# main.net
KiCad netlist of a schematic drawn in EAGLE
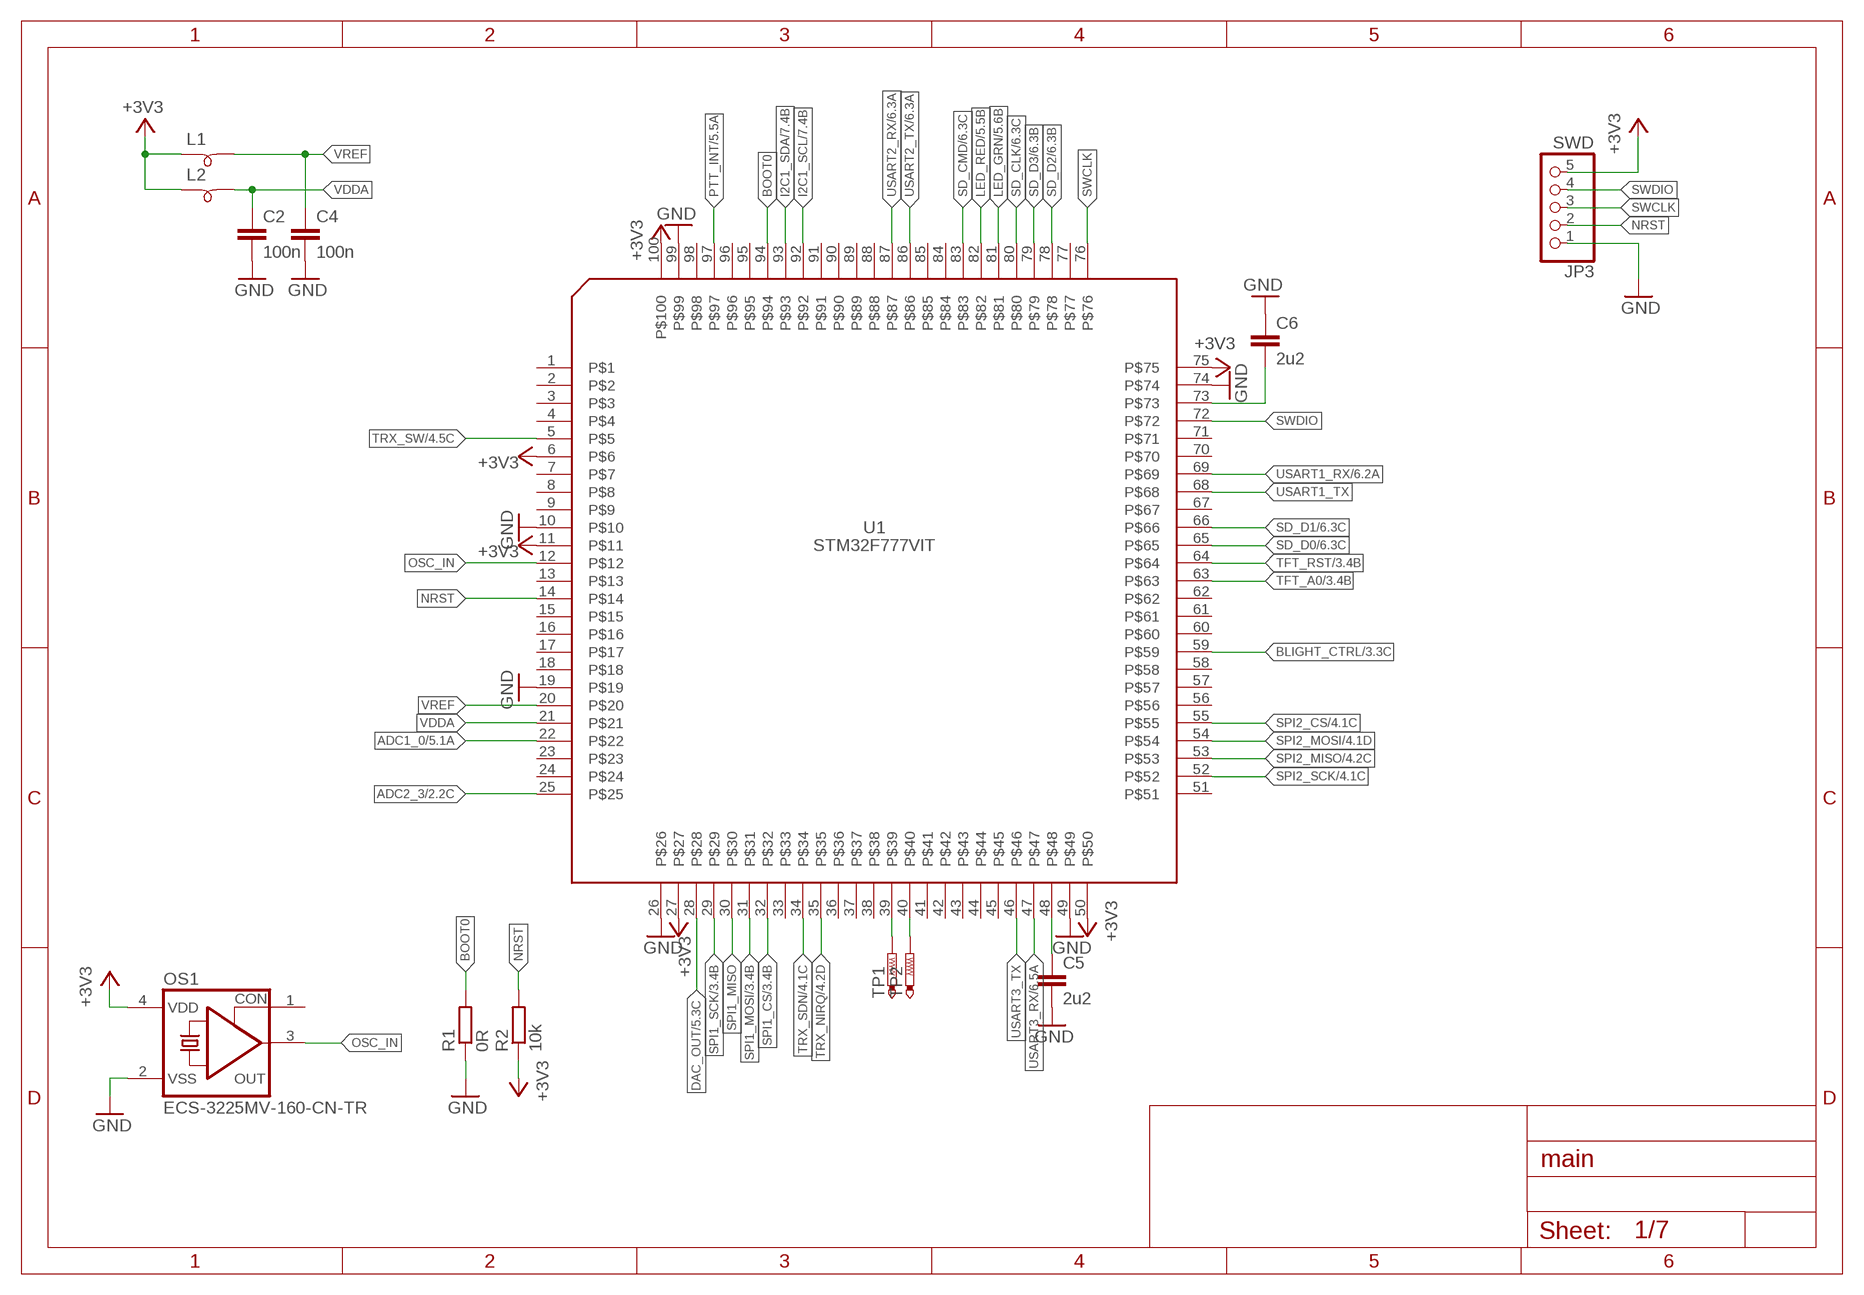
[diagram p0: schematic, sheet 1]
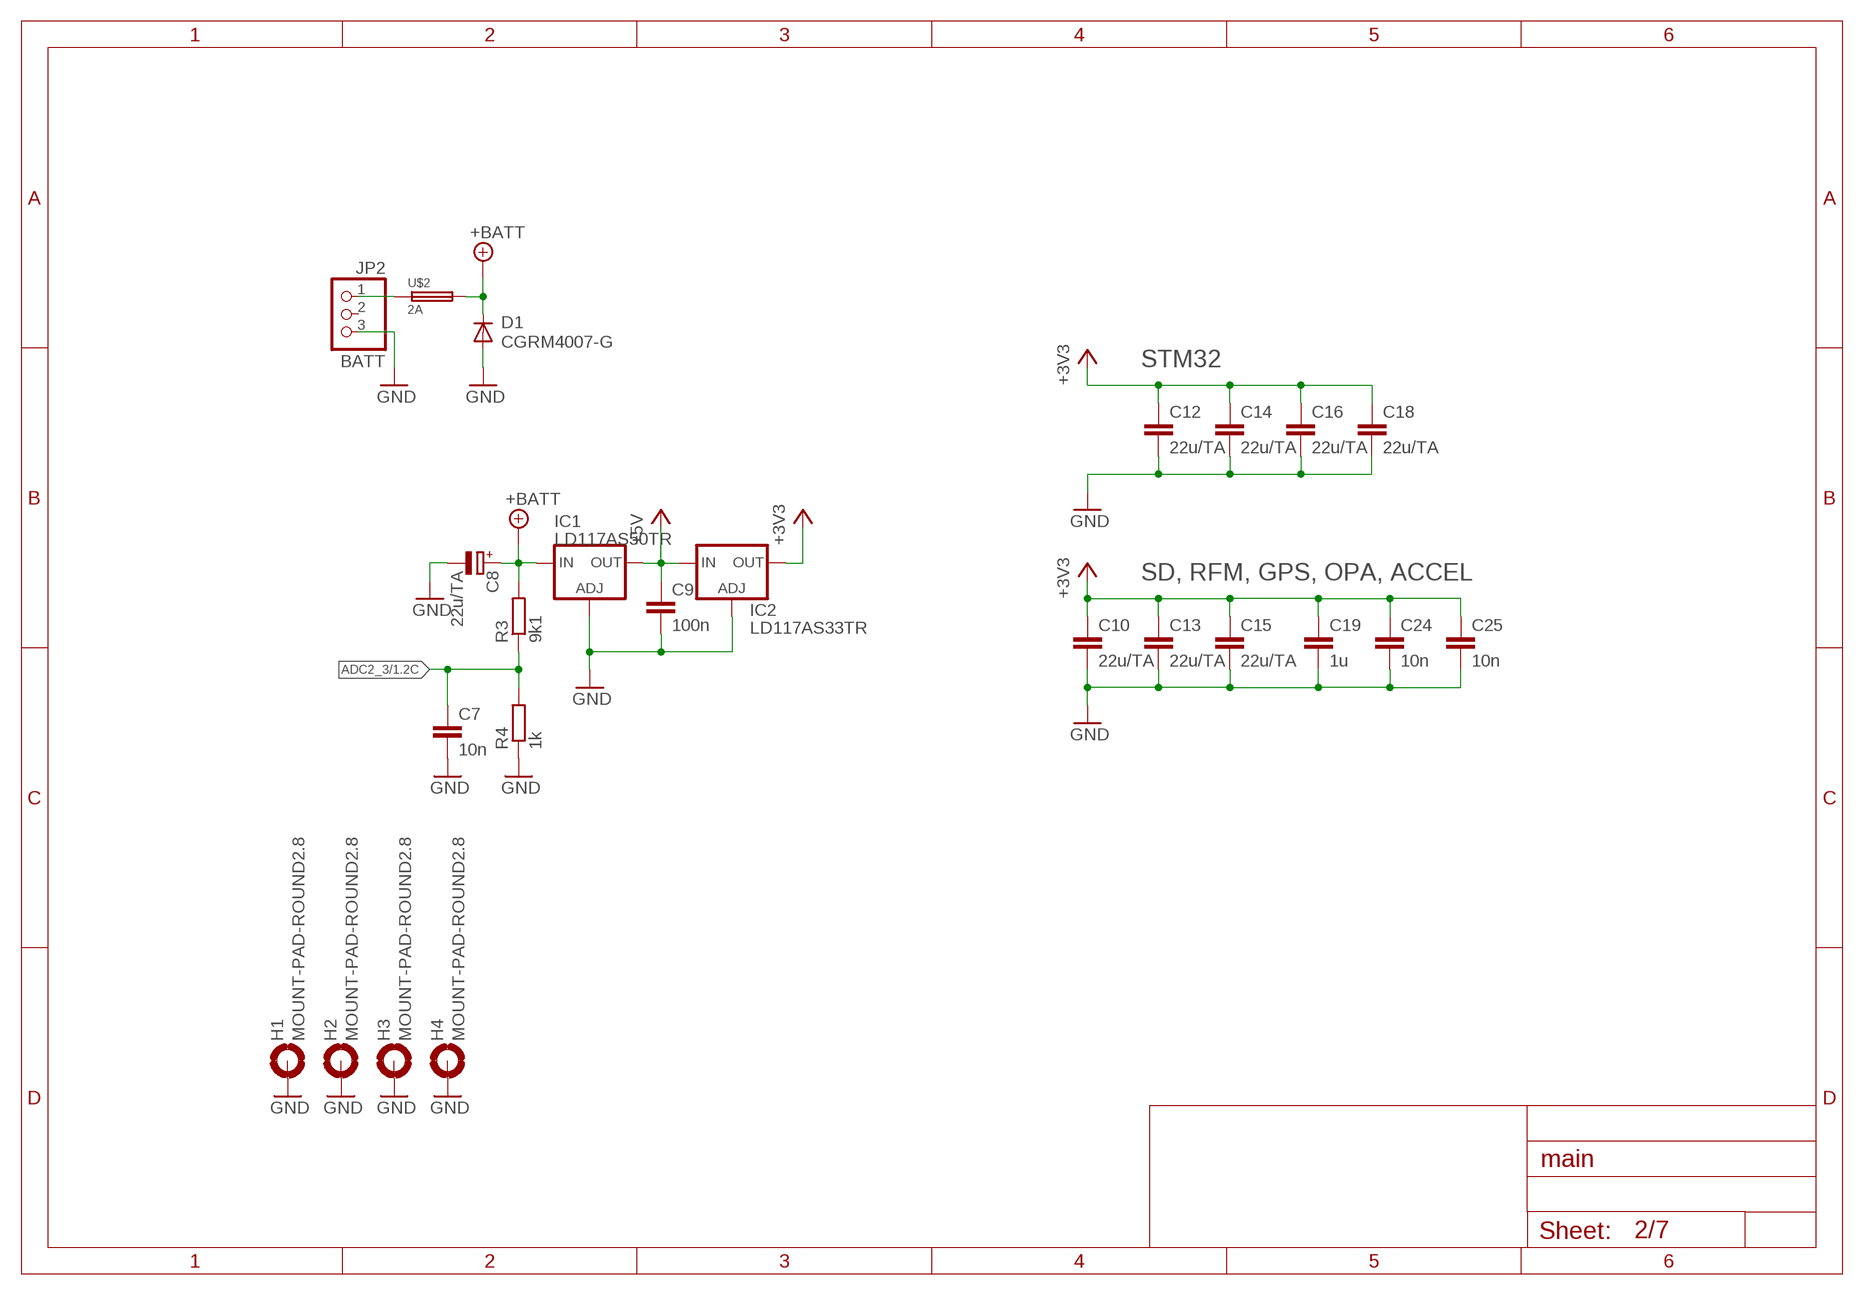
[diagram p1: schematic, sheet 2]
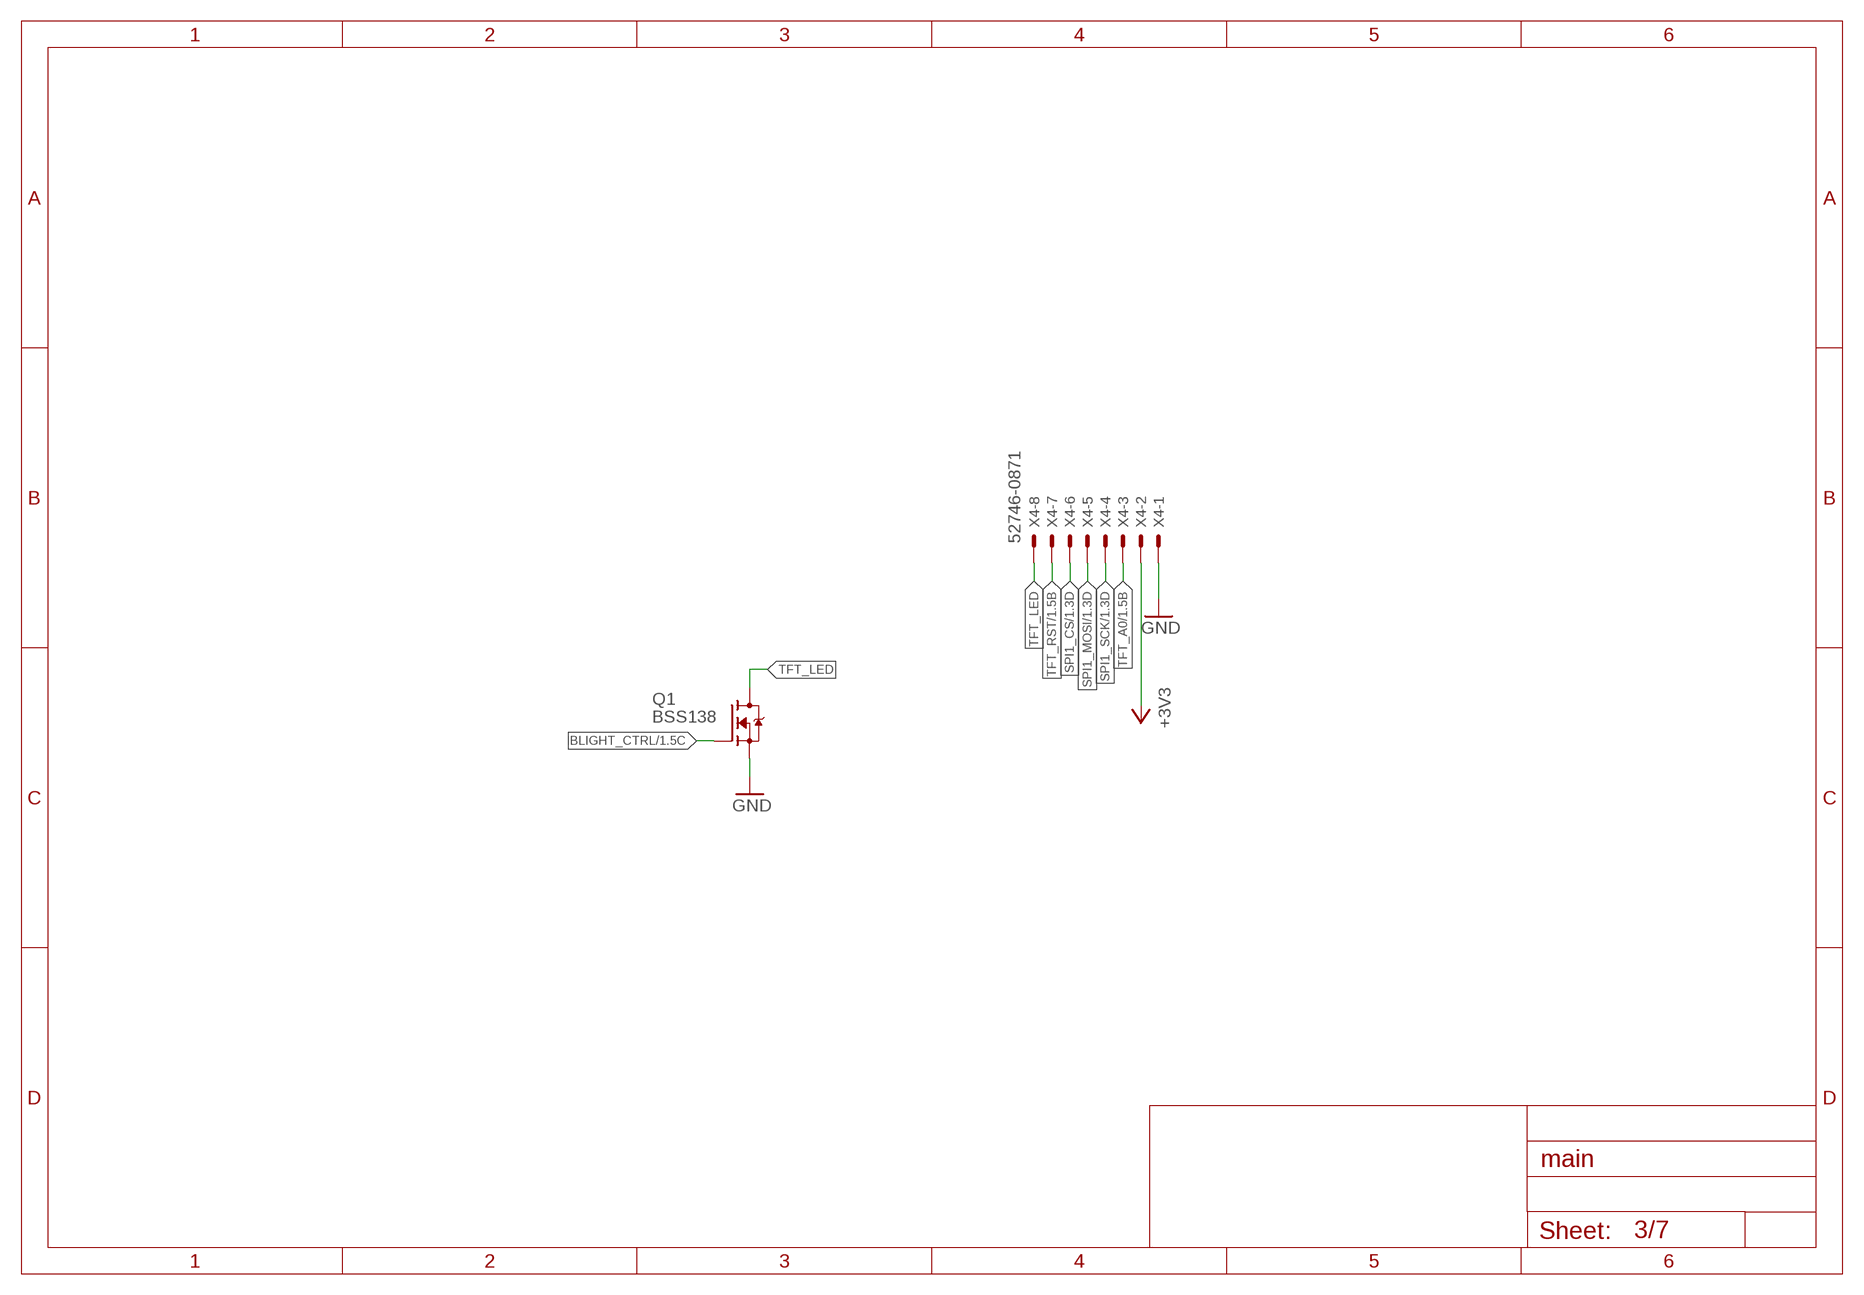
[diagram p2: schematic, sheet 3]
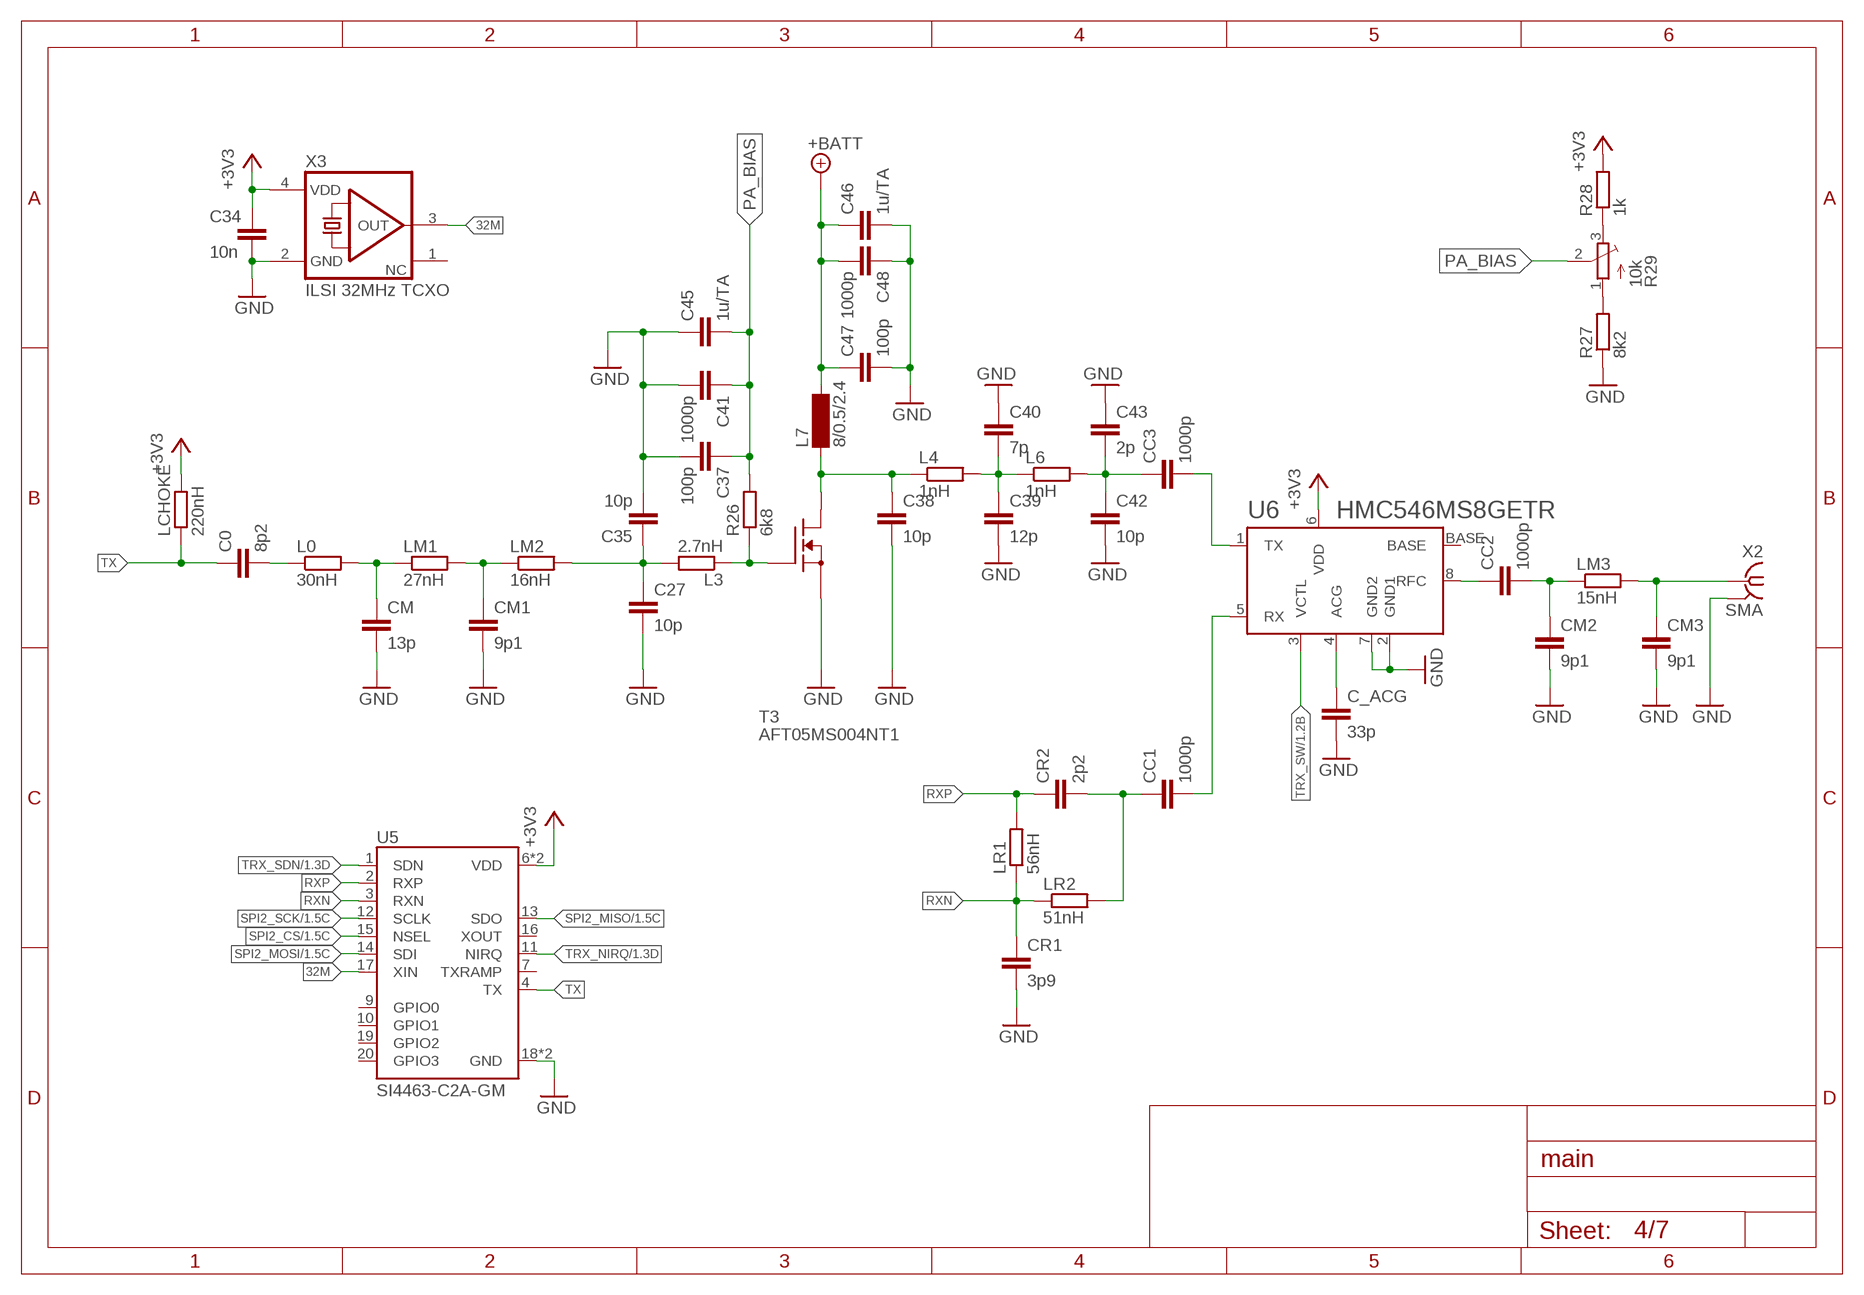
[diagram p3: schematic, sheet 4]
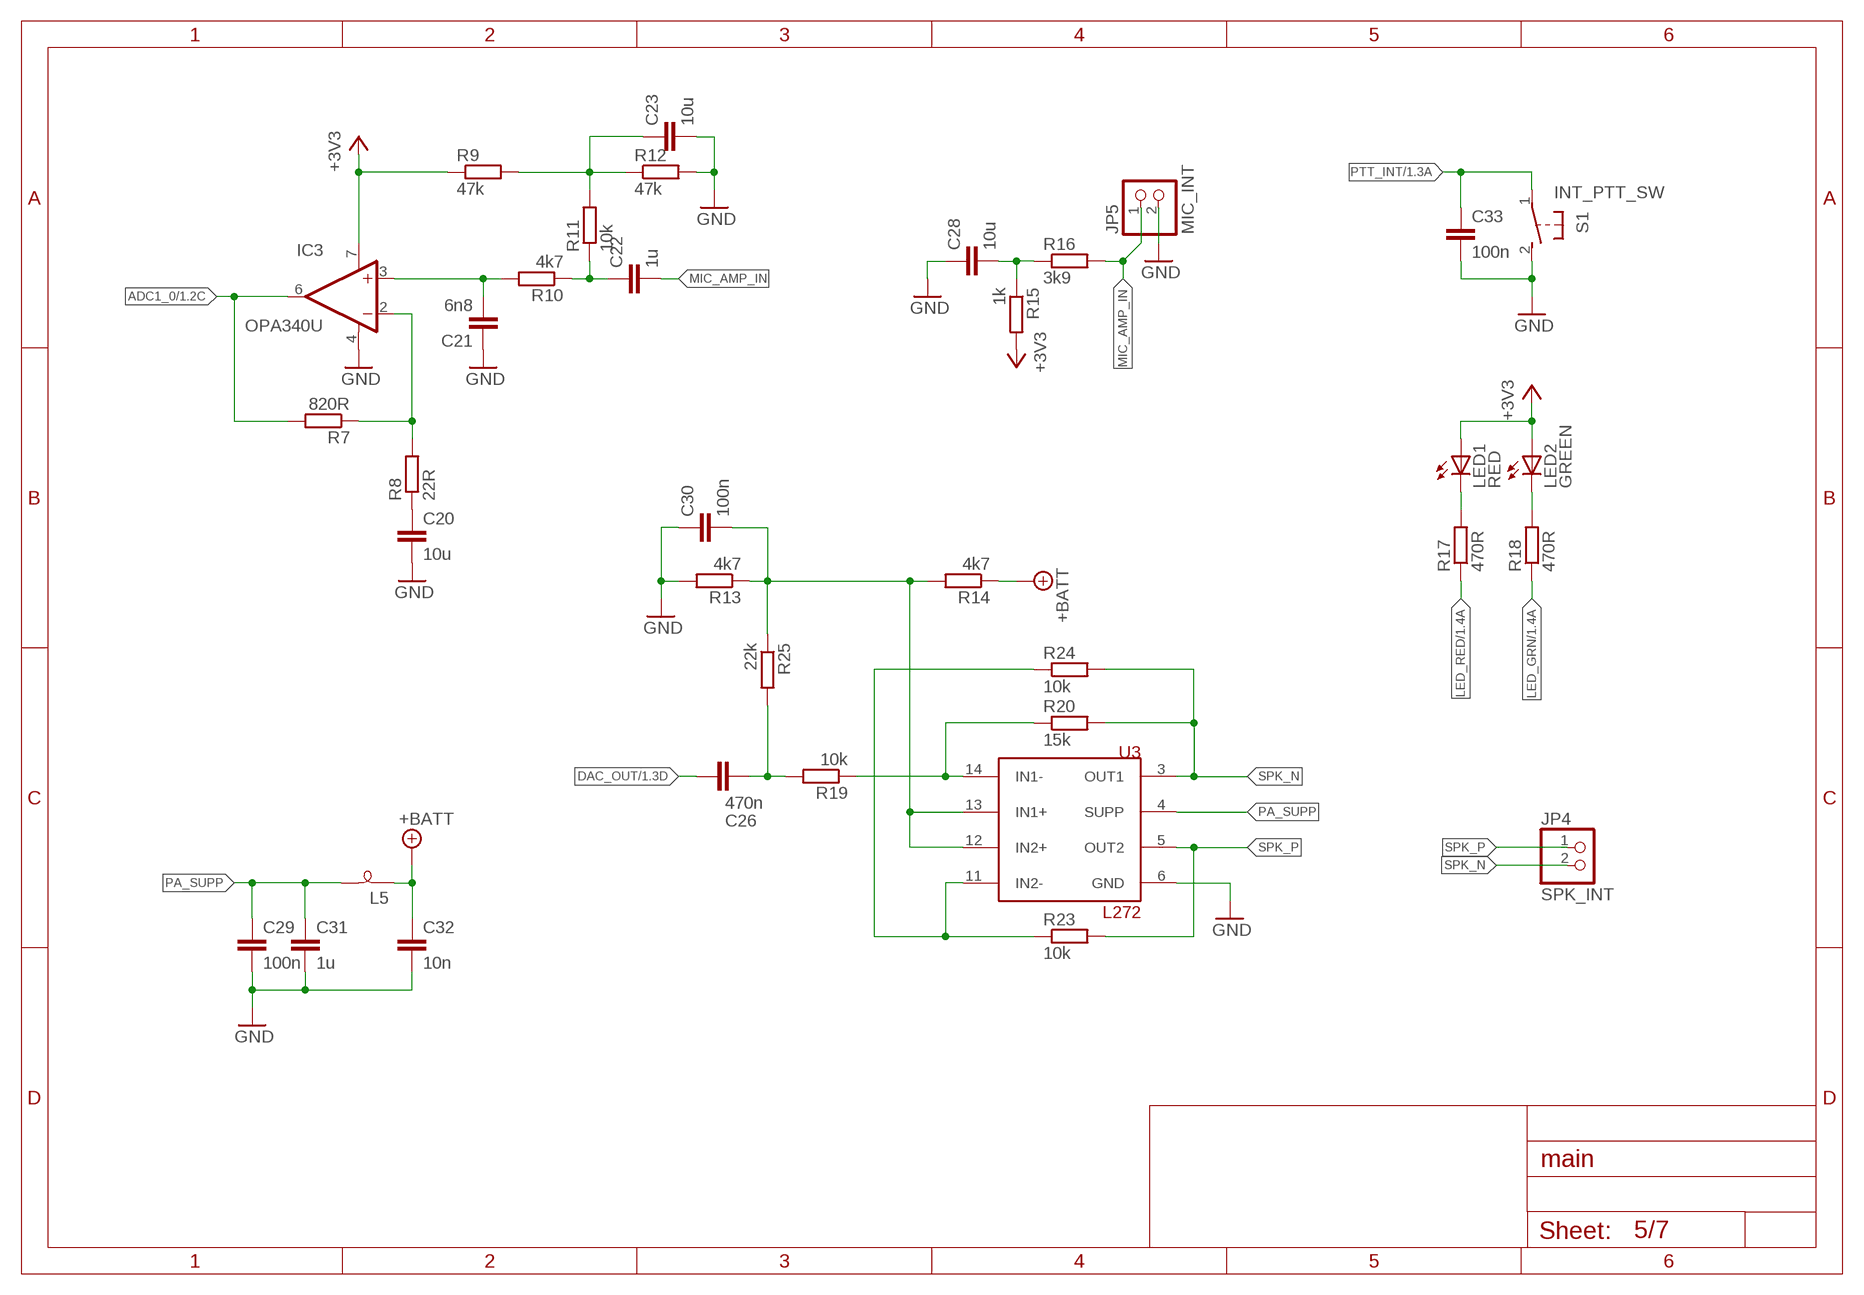
[diagram p4: schematic, sheet 5]
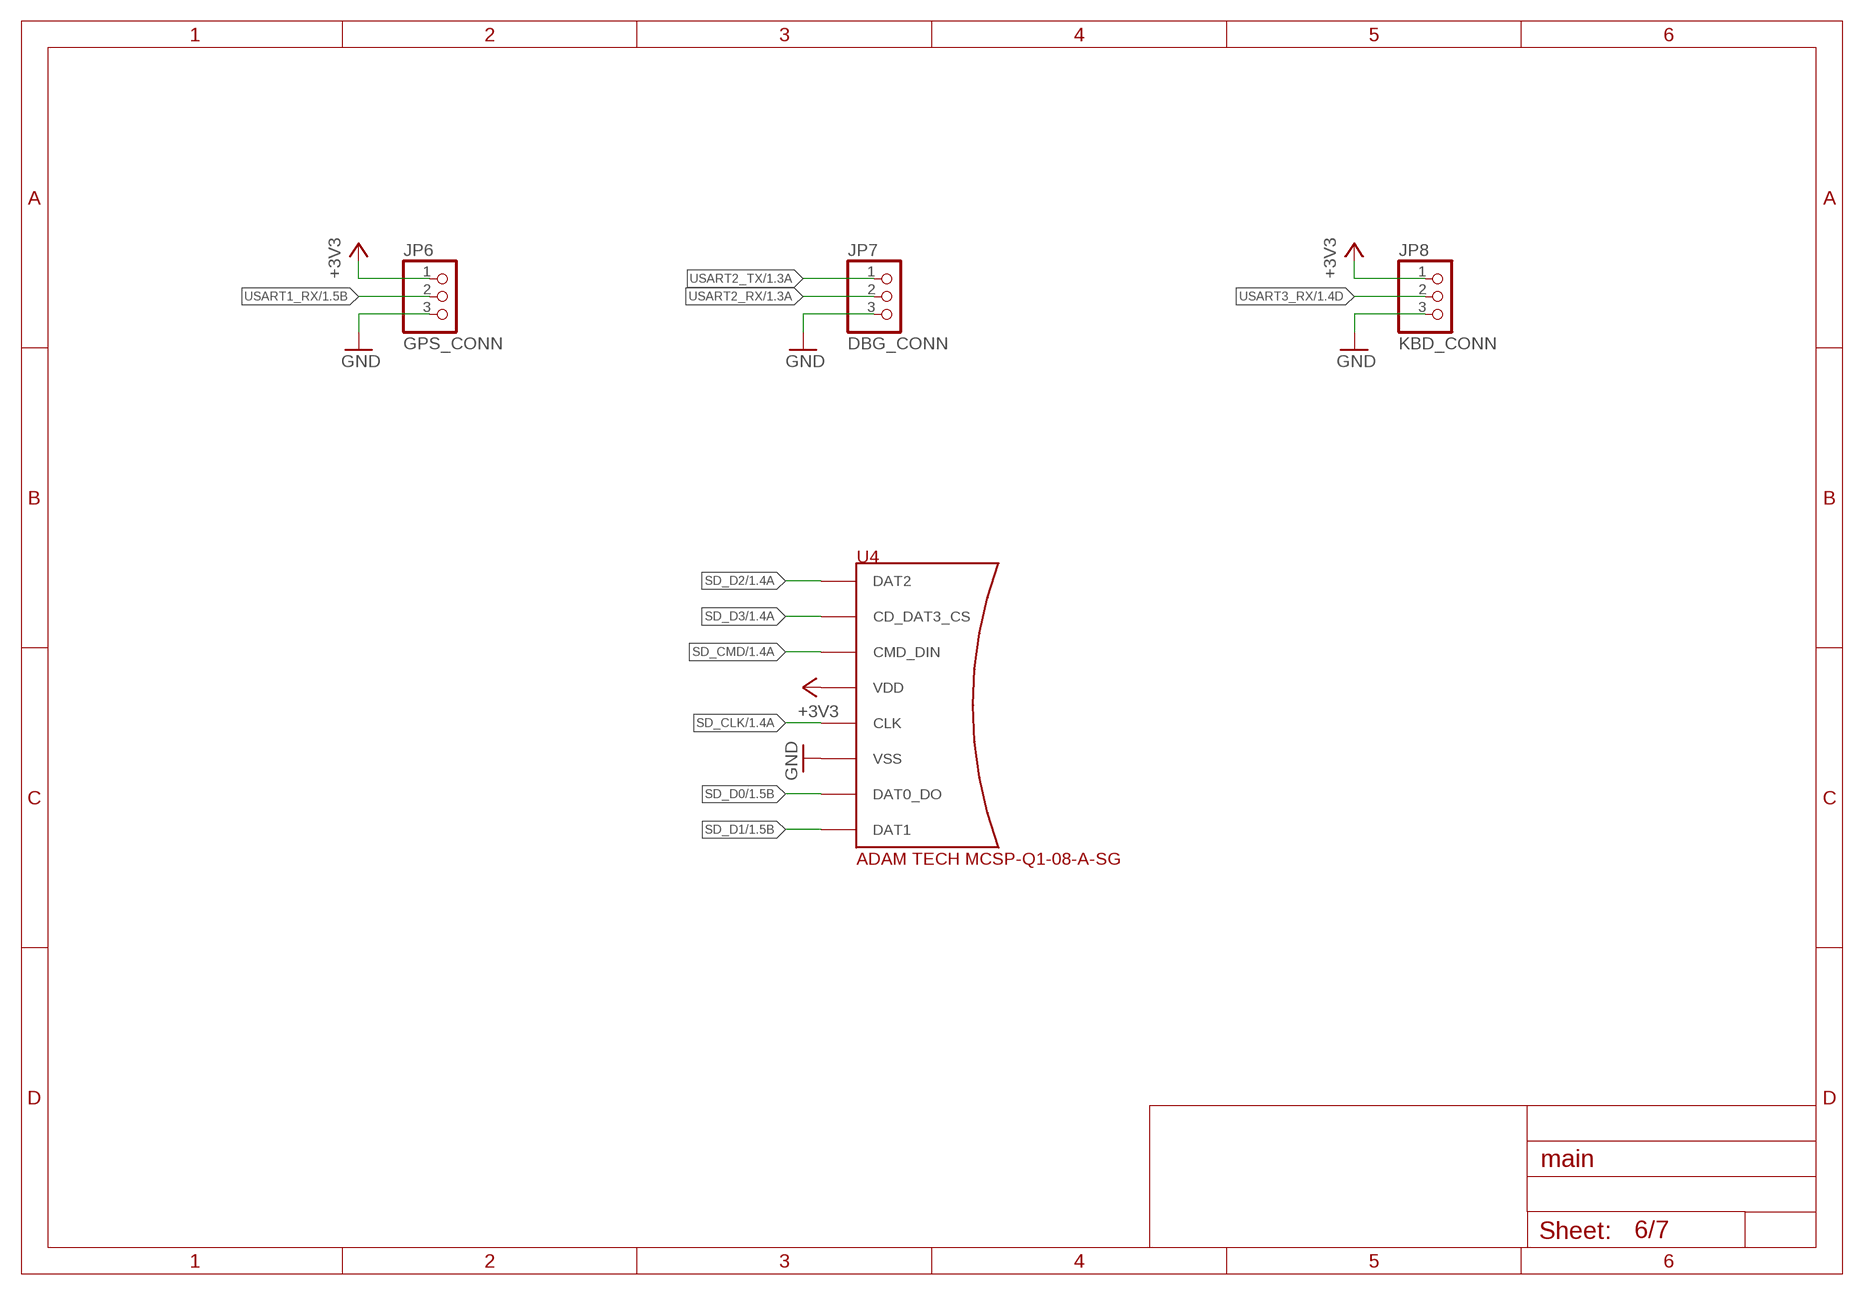
[diagram p5: schematic, sheet 6]
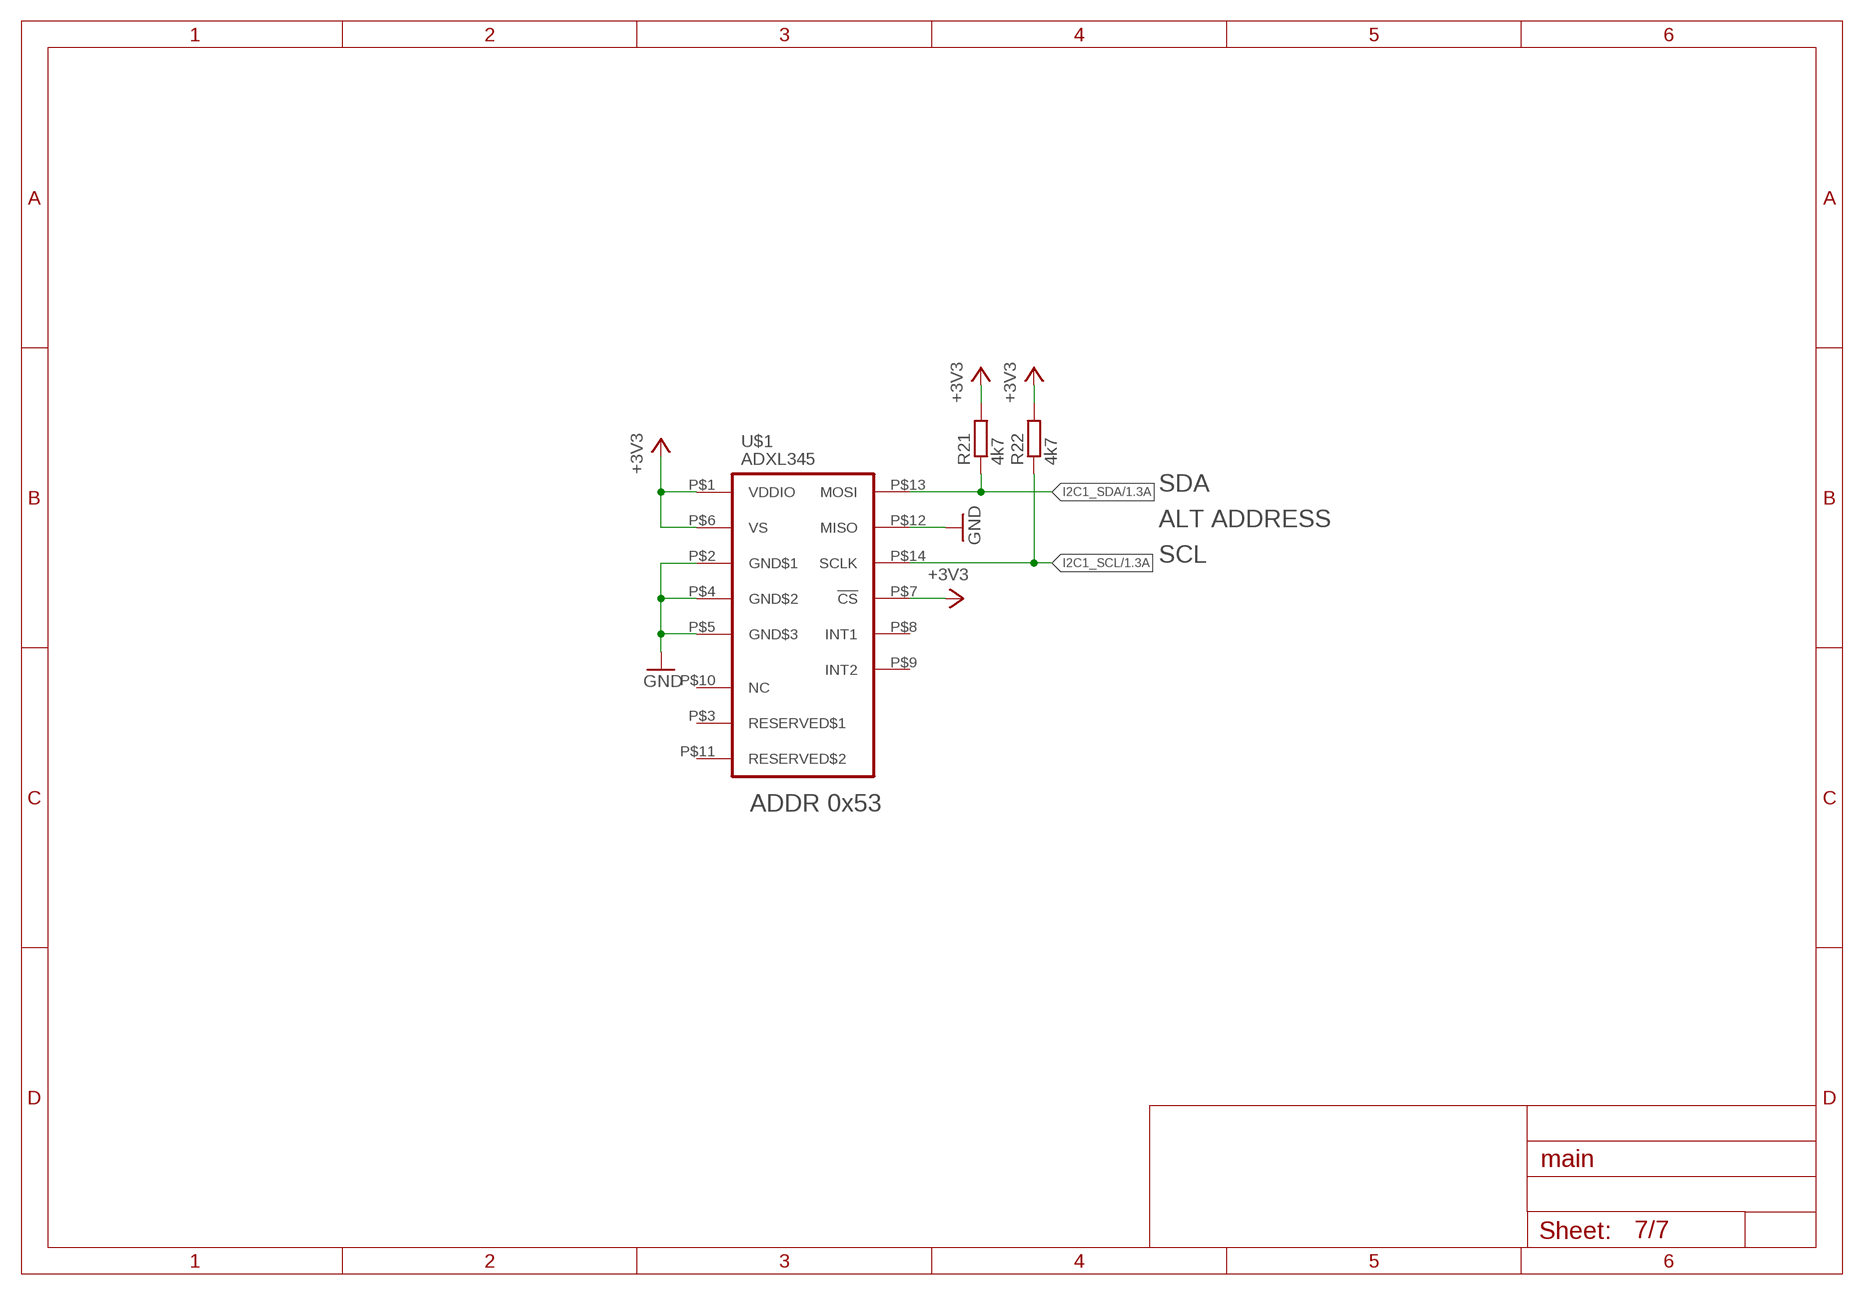
[diagram p6: schematic, sheet 7]

(export (version "E")
  (design (tool "Eeschema 10.0.6"))
  (components
    (comp (ref "C20")
      (value "10u")
      (footprint "eagle-import:C1206")
      (libsource (lib "eagle-import") (part "C-EUC1206"))
    )
    (comp (ref "C21")
      (value "6n8")
      (footprint "eagle-import:C0805")
      (libsource (lib "eagle-import") (part "C-EUC0805"))
    )
    (comp (ref "C22")
      (value "1u")
      (footprint "eagle-import:C1206")
      (libsource (lib "eagle-import") (part "C-EUC1206"))
    )
    (comp (ref "C23")
      (value "10u")
      (footprint "eagle-import:C1206")
      (libsource (lib "eagle-import") (part "C-EUC1206"))
    )
    (comp (ref "C26")
      (value "470n")
      (footprint "eagle-import:C0805")
      (libsource (lib "eagle-import") (part "C-EUC0805"))
    )
    (comp (ref "C28")
      (value "10u")
      (footprint "eagle-import:C1206")
      (libsource (lib "eagle-import") (part "C-EUC1206"))
    )
    (comp (ref "C29")
      (value "100n")
      (footprint "eagle-import:C1206")
      (libsource (lib "eagle-import") (part "C-EUC1206"))
    )
    (comp (ref "C30")
      (value "100n")
      (footprint "eagle-import:C1206")
      (libsource (lib "eagle-import") (part "C-EUC1206"))
    )
    (comp (ref "C31")
      (value "1u")
      (footprint "eagle-import:C1206")
      (libsource (lib "eagle-import") (part "C-EUC1206"))
    )
    (comp (ref "C32")
      (value "10n")
      (footprint "eagle-import:C0805")
      (libsource (lib "eagle-import") (part "C-EUC0805"))
    )
    (comp (ref "C33")
      (value "100n")
      (footprint "eagle-import:C0805")
      (libsource (lib "eagle-import") (part "C-EUC0805"))
    )
    (comp (ref "IC3")
      (value "OPA340U")
      (footprint "eagle-import:SO08")
      (fields (field (name "MPN") "OPA340UA"))
      (libsource (lib "eagle-import") (part "OPA340U"))
    )
    (comp (ref "JP4")
      (value "SPK_INT")
      (footprint "eagle-import:1X02")
      (libsource (lib "eagle-import") (part "PINHD-1X2"))
    )
    (comp (ref "JP5")
      (value "MIC_INT")
      (footprint "eagle-import:1X02")
      (libsource (lib "eagle-import") (part "PINHD-1X2"))
    )
    (comp (ref "L5")
      (value "SM-B5")
      (footprint "eagle-import:SM-B5")
      (libsource (lib "eagle-import") (part "SM-B5"))
    )
    (comp (ref "LED1")
      (value "RED")
      (footprint "eagle-import:CHIPLED_1206")
      (libsource (lib "eagle-import") (part "LEDCHIPLED_1206"))
    )
    (comp (ref "LED2")
      (value "GREEN")
      (footprint "eagle-import:CHIPLED_1206")
      (libsource (lib "eagle-import") (part "LEDCHIPLED_1206"))
    )
    (comp (ref "R7")
      (value "820R")
      (footprint "eagle-import:R0805")
      (libsource (lib "eagle-import") (part "resistor_R-EU_R0805"))
    )
    (comp (ref "R8")
      (value "22R")
      (footprint "eagle-import:R0805")
      (libsource (lib "eagle-import") (part "resistor_R-EU_R0805"))
    )
    (comp (ref "R9")
      (value "47k")
      (footprint "eagle-import:R0805")
      (libsource (lib "eagle-import") (part "resistor_R-EU_R0805"))
    )
    (comp (ref "R10")
      (value "4k7")
      (footprint "eagle-import:R0805")
      (libsource (lib "eagle-import") (part "resistor_R-EU_R0805"))
    )
    (comp (ref "R11")
      (value "10k")
      (footprint "eagle-import:R0805")
      (libsource (lib "eagle-import") (part "resistor_R-EU_R0805"))
    )
    (comp (ref "R12")
      (value "47k")
      (footprint "eagle-import:R0805")
      (libsource (lib "eagle-import") (part "resistor_R-EU_R0805"))
    )
    (comp (ref "R13")
      (value "4k7")
      (footprint "eagle-import:R0805")
      (libsource (lib "eagle-import") (part "resistor_R-EU_R0805"))
    )
    (comp (ref "R14")
      (value "4k7")
      (footprint "eagle-import:R0805")
      (libsource (lib "eagle-import") (part "resistor_R-EU_R0805"))
    )
    (comp (ref "R15")
      (value "1k")
      (footprint "eagle-import:R0805")
      (libsource (lib "eagle-import") (part "resistor_R-EU_R0805"))
    )
    (comp (ref "R16")
      (value "3k9")
      (footprint "eagle-import:R0805")
      (libsource (lib "eagle-import") (part "resistor_R-EU_R0805"))
    )
    (comp (ref "R17")
      (value "470R")
      (footprint "eagle-import:R0805")
      (libsource (lib "eagle-import") (part "resistor_R-EU_R0805"))
    )
    (comp (ref "R18")
      (value "470R")
      (footprint "eagle-import:R0805")
      (libsource (lib "eagle-import") (part "resistor_R-EU_R0805"))
    )
    (comp (ref "R19")
      (value "10k")
      (footprint "eagle-import:R0805")
      (libsource (lib "eagle-import") (part "resistor_R-EU_R0805"))
    )
    (comp (ref "R20")
      (value "15k")
      (footprint "eagle-import:R0805")
      (libsource (lib "eagle-import") (part "resistor_R-EU_R0805"))
    )
    (comp (ref "R23")
      (value "10k")
      (footprint "eagle-import:R0805")
      (libsource (lib "eagle-import") (part "resistor_R-EU_R0805"))
    )
    (comp (ref "R24")
      (value "10k")
      (footprint "eagle-import:R0805")
      (libsource (lib "eagle-import") (part "resistor_R-EU_R0805"))
    )
    (comp (ref "R25")
      (value "22k")
      (footprint "eagle-import:R0805")
      (libsource (lib "eagle-import") (part "resistor_R-EU_R0805"))
    )
    (comp (ref "S1")
      (value "INT_PTT_SW")
      (footprint "eagle-import:B3F-31XX")
      (fields (field (name "MPN") "B3F-3100"))
      (libsource (lib "eagle-import") (part "31-XX"))
    )
    (comp (ref "U3")
      (value "L272")
      (footprint "eagle-import:SO16")
      (libsource (lib "eagle-import") (part "L272"))
    )
    (comp (ref "R21")
      (value "4k7")
      (footprint "eagle-import:R0805")
      (libsource (lib "eagle-import") (part "R-EU_R0805"))
    )
    (comp (ref "R22")
      (value "4k7")
      (footprint "eagle-import:R0805")
      (libsource (lib "eagle-import") (part "R-EU_R0805"))
    )
    (comp (ref "U$1")
      (value "ADXL345")
      (footprint "eagle-import:LGA14")
      (libsource (lib "eagle-import") (part "ADXL345"))
    )
    (comp (ref "Q1")
      (value "BSS138")
      (footprint "eagle-import:SOT23")
      (fields (field (name "MF") "Fairchild"))
      (libsource (lib "eagle-import") (part "BSS138"))
    )
    (comp (ref "X4")
      (value "52746-0871")
      (footprint "eagle-import:52745-0890")
      (fields (field (name "MPN") "52745-0890"))
      (libsource (lib "eagle-import") (part "52745-0890"))
    )
    (comp (ref "C2")
      (value "100n")
      (footprint "eagle-import:C0805")
      (libsource (lib "eagle-import") (part "C-EUC0805"))
    )
    (comp (ref "C4")
      (value "100n")
      (footprint "eagle-import:C0805")
      (libsource (lib "eagle-import") (part "C-EUC0805"))
    )
    (comp (ref "C5")
      (value "2u2")
      (footprint "eagle-import:C1206")
      (libsource (lib "eagle-import") (part "C-EUC1206"))
    )
    (comp (ref "C6")
      (value "2u2")
      (footprint "eagle-import:C1206")
      (libsource (lib "eagle-import") (part "C-EUC1206"))
    )
    (comp (ref "JP3")
      (value "SWD")
      (footprint "eagle-import:1X05_90")
      (libsource (lib "eagle-import") (part "PINHD-1X5/90"))
    )
    (comp (ref "L1")
      (value "SM-B5")
      (footprint "eagle-import:SM-B5")
      (libsource (lib "eagle-import") (part "SM-B5"))
    )
    (comp (ref "L2")
      (value "SM-B5")
      (footprint "eagle-import:SM-B5")
      (libsource (lib "eagle-import") (part "SM-B5"))
    )
    (comp (ref "OS1")
      (value "ECS-3225MV-160-CN-TR")
      (footprint "eagle-import:3.4X2.7-4-PAD")
      (libsource (lib "eagle-import") (part "OSC-OE-CFPS-39"))
    )
    (comp (ref "R1")
      (value "0R")
      (footprint "eagle-import:R0805")
      (libsource (lib "eagle-import") (part "resistor_R-EU_R0805"))
    )
    (comp (ref "R2")
      (value "10k")
      (footprint "eagle-import:R0805")
      (libsource (lib "eagle-import") (part "resistor_R-EU_R0805"))
    )
    (comp (ref "TP1")
      (value "PTR1B1,27")
      (footprint "eagle-import:B1,27")
      (libsource (lib "eagle-import") (part "PTR1B1,27"))
    )
    (comp (ref "TP2")
      (value "PTR1B1,27")
      (footprint "eagle-import:B1,27")
      (libsource (lib "eagle-import") (part "PTR1B1,27"))
    )
    (comp (ref "U1")
      (value "STM32F777VIT")
      (footprint "eagle-import:LQFP100")
      (libsource (lib "eagle-import") (part "STM32F777VIT"))
    )
    (comp (ref "C0")
      (value "8p2")
      (footprint "eagle-import:C0805")
      (libsource (lib "eagle-import") (part "C-EUC0805"))
    )
    (comp (ref "C27")
      (value "10p")
      (footprint "eagle-import:C0805")
      (libsource (lib "eagle-import") (part "C-EUC0805"))
    )
    (comp (ref "C34")
      (value "10n")
      (footprint "eagle-import:C0805")
      (libsource (lib "eagle-import") (part "C-EUC0805"))
    )
    (comp (ref "C35")
      (value "10p")
      (footprint "eagle-import:C0805")
      (libsource (lib "eagle-import") (part "C-EUC0805"))
    )
    (comp (ref "C37")
      (value "100p")
      (footprint "eagle-import:C0805")
      (libsource (lib "eagle-import") (part "C-EUC0805"))
    )
    (comp (ref "C38")
      (value "10p")
      (footprint "eagle-import:C0805")
      (libsource (lib "eagle-import") (part "C-EUC0805"))
    )
    (comp (ref "C39")
      (value "12p")
      (footprint "eagle-import:C0805")
      (libsource (lib "eagle-import") (part "C-EUC0805"))
    )
    (comp (ref "C40")
      (value "7p")
      (footprint "eagle-import:C0805")
      (libsource (lib "eagle-import") (part "C-EUC0805"))
    )
    (comp (ref "C41")
      (value "1000p")
      (footprint "eagle-import:C0805")
      (libsource (lib "eagle-import") (part "C-EUC0805"))
    )
    (comp (ref "C42")
      (value "10p")
      (footprint "eagle-import:C0805")
      (libsource (lib "eagle-import") (part "C-EUC0805"))
    )
    (comp (ref "C43")
      (value "2p")
      (footprint "eagle-import:C0805")
      (libsource (lib "eagle-import") (part "C-EUC0805"))
    )
    (comp (ref "C45")
      (value "1u/TA")
      (footprint "eagle-import:C1206")
      (libsource (lib "eagle-import") (part "resistor_C-EUC1206"))
    )
    (comp (ref "C46")
      (value "1u/TA")
      (footprint "eagle-import:C1206")
      (libsource (lib "eagle-import") (part "resistor_C-EUC1206"))
    )
    (comp (ref "C47")
      (value "100p")
      (footprint "eagle-import:C0805")
      (libsource (lib "eagle-import") (part "C-EUC0805"))
    )
    (comp (ref "C48")
      (value "1000p")
      (footprint "eagle-import:C0805")
      (libsource (lib "eagle-import") (part "C-EUC0805"))
    )
    (comp (ref "CC1")
      (value "1000p")
      (footprint "eagle-import:C0805")
      (libsource (lib "eagle-import") (part "C-EUC0805"))
    )
    (comp (ref "CC2")
      (value "1000p")
      (footprint "eagle-import:C0805")
      (libsource (lib "eagle-import") (part "C-EUC0805"))
    )
    (comp (ref "CC3")
      (value "1000p")
      (footprint "eagle-import:C0805")
      (libsource (lib "eagle-import") (part "C-EUC0805"))
    )
    (comp (ref "CM")
      (value "13p")
      (footprint "eagle-import:C0805")
      (libsource (lib "eagle-import") (part "C-EUC0805"))
    )
    (comp (ref "CM1")
      (value "9p1")
      (footprint "eagle-import:C0805")
      (libsource (lib "eagle-import") (part "C-EUC0805"))
    )
    (comp (ref "CM2")
      (value "9p1")
      (footprint "eagle-import:C0805")
      (libsource (lib "eagle-import") (part "C-EUC0805"))
    )
    (comp (ref "CM3")
      (value "9p1")
      (footprint "eagle-import:C0805")
      (libsource (lib "eagle-import") (part "C-EUC0805"))
    )
    (comp (ref "CR1")
      (value "3p9")
      (footprint "eagle-import:C0805")
      (libsource (lib "eagle-import") (part "C-EUC0805"))
    )
    (comp (ref "CR2")
      (value "2p2")
      (footprint "eagle-import:C0805")
      (libsource (lib "eagle-import") (part "C-EUC0805"))
    )
    (comp (ref "C_ACG")
      (value "33p")
      (footprint "eagle-import:C0805")
      (libsource (lib "eagle-import") (part "C-EUC0805"))
    )
    (comp (ref "L0")
      (value "30nH")
      (footprint "eagle-import:R0805")
      (libsource (lib "eagle-import") (part "resistor_R-EU_R0805"))
    )
    (comp (ref "L3")
      (value "2.7nH")
      (footprint "eagle-import:R0805")
      (libsource (lib "eagle-import") (part "R-EU_R0805"))
    )
    (comp (ref "L4")
      (value "1nH")
      (footprint "eagle-import:R0603")
      (libsource (lib "eagle-import") (part "resistor_R-EU_R0603"))
    )
    (comp (ref "L6")
      (value "1nH")
      (footprint "eagle-import:R0603")
      (libsource (lib "eagle-import") (part "resistor_R-EU_R0603"))
    )
    (comp (ref "L7")
      (value "8/0.5/2.4")
      (footprint "eagle-import:SM-L15B")
      (libsource (lib "eagle-import") (part "AIR_COIL"))
    )
    (comp (ref "LCHOKE")
      (value "220nH")
      (footprint "eagle-import:R0805")
      (libsource (lib "eagle-import") (part "resistor_R-EU_R0805"))
    )
    (comp (ref "LM1")
      (value "27nH")
      (footprint "eagle-import:R0805")
      (libsource (lib "eagle-import") (part "resistor_R-EU_R0805"))
    )
    (comp (ref "LM2")
      (value "16nH")
      (footprint "eagle-import:R0805")
      (libsource (lib "eagle-import") (part "resistor_R-EU_R0805"))
    )
    (comp (ref "LM3")
      (value "15nH")
      (footprint "eagle-import:R0805")
      (libsource (lib "eagle-import") (part "resistor_R-EU_R0805"))
    )
    (comp (ref "LR1")
      (value "56nH")
      (footprint "eagle-import:R0805")
      (libsource (lib "eagle-import") (part "resistor_R-EU_R0805"))
    )
    (comp (ref "LR2")
      (value "51nH")
      (footprint "eagle-import:R0805")
      (libsource (lib "eagle-import") (part "resistor_R-EU_R0805"))
    )
    (comp (ref "R26")
      (value "6k8")
      (footprint "eagle-import:R0805")
      (libsource (lib "eagle-import") (part "R-EU_R0805"))
    )
    (comp (ref "R27")
      (value "8k2")
      (footprint "eagle-import:R0805")
      (libsource (lib "eagle-import") (part "R-EU_R0805"))
    )
    (comp (ref "R28")
      (value "1k")
      (footprint "eagle-import:R0805")
      (libsource (lib "eagle-import") (part "R-EU_R0805"))
    )
    (comp (ref "R29")
      (value "10k")
      (footprint "eagle-import:3223W")
      (libsource (lib "eagle-import") (part "TRIM_EU-3223W"))
    )
    (comp (ref "T3")
      (value "AFT05MS004NT1")
      (footprint "eagle-import:SOT89-BCE")
      (libsource (lib "eagle-import") (part "AFT05MS004NT1"))
    )
    (comp (ref "U5")
      (value "SI4463-C2A-GM")
      (footprint "eagle-import:QFN50P400X400X90-20N")
      (fields (field (name "MF") "Silicon Labs"))
      (libsource (lib "eagle-import") (part "SI4463-C2A-GM"))
    )
    (comp (ref "U6")
      (value "HMC546MS8GETR")
      (footprint "eagle-import:SOP65P490X110-8N")
      (libsource (lib "eagle-import") (part "HMC546MS8GETR"))
    )
    (comp (ref "X2")
      (value "SMA")
      (footprint "eagle-import:J502-ND-142-0701-871_876")
      (fields (field (name "MF") "JOHNSON COMPONENTS") (field (name "MPN") "142-0701-871"))
      (libsource (lib "eagle-import") (part "SMA-142-0701-871/876"))
    )
    (comp (ref "X3")
      (value "ILSI 32MHz TCXO")
      (footprint "eagle-import:ASE")
      (libsource (lib "eagle-import") (part "ASE"))
    )
    (comp (ref "C7")
      (value "10n")
      (footprint "eagle-import:C0805")
      (libsource (lib "eagle-import") (part "resistor_C-EUC0805"))
    )
    (comp (ref "C8")
      (value "22u/TA")
      (footprint "eagle-import:SMC_C")
      (libsource (lib "eagle-import") (part "CPOL-EUSMCC"))
    )
    (comp (ref "C9")
      (value "100n")
      (footprint "eagle-import:C1206")
      (libsource (lib "eagle-import") (part "resistor_C-EUC1206"))
    )
    (comp (ref "C10")
      (value "22u/TA")
      (footprint "eagle-import:C1206")
      (libsource (lib "eagle-import") (part "resistor_C-EUC1206"))
    )
    (comp (ref "C12")
      (value "22u/TA")
      (footprint "eagle-import:C1206")
      (libsource (lib "eagle-import") (part "resistor_C-EUC1206"))
    )
    (comp (ref "C13")
      (value "22u/TA")
      (footprint "eagle-import:C1206")
      (libsource (lib "eagle-import") (part "resistor_C-EUC1206"))
    )
    (comp (ref "C14")
      (value "22u/TA")
      (footprint "eagle-import:C1206")
      (libsource (lib "eagle-import") (part "resistor_C-EUC1206"))
    )
    (comp (ref "C15")
      (value "22u/TA")
      (footprint "eagle-import:C1206")
      (libsource (lib "eagle-import") (part "resistor_C-EUC1206"))
    )
    (comp (ref "C16")
      (value "22u/TA")
      (footprint "eagle-import:C1206")
      (libsource (lib "eagle-import") (part "resistor_C-EUC1206"))
    )
    (comp (ref "C18")
      (value "22u/TA")
      (footprint "eagle-import:C1206")
      (libsource (lib "eagle-import") (part "resistor_C-EUC1206"))
    )
    (comp (ref "C19")
      (value "1u")
      (footprint "eagle-import:C1206")
      (libsource (lib "eagle-import") (part "C-EUC1206"))
    )
    (comp (ref "C24")
      (value "10n")
      (footprint "eagle-import:C0805")
      (libsource (lib "eagle-import") (part "resistor_C-EUC0805"))
    )
    (comp (ref "C25")
      (value "10n")
      (footprint "eagle-import:C0805")
      (libsource (lib "eagle-import") (part "resistor_C-EUC0805"))
    )
    (comp (ref "D1")
      (value "CGRM4007-G")
      (footprint "eagle-import:SOD-123_MINI-SMA")
      (libsource (lib "eagle-import") (part "CGRM400-G7"))
    )
    (comp (ref "H1")
      (value "MOUNT-PAD-ROUND2.8")
      (footprint "eagle-import:2,8-PAD")
      (libsource (lib "eagle-import") (part "MOUNT-PAD-ROUND2.8"))
    )
    (comp (ref "H2")
      (value "MOUNT-PAD-ROUND2.8")
      (footprint "eagle-import:2,8-PAD")
      (libsource (lib "eagle-import") (part "MOUNT-PAD-ROUND2.8"))
    )
    (comp (ref "H3")
      (value "MOUNT-PAD-ROUND2.8")
      (footprint "eagle-import:2,8-PAD")
      (libsource (lib "eagle-import") (part "MOUNT-PAD-ROUND2.8"))
    )
    (comp (ref "H4")
      (value "MOUNT-PAD-ROUND2.8")
      (footprint "eagle-import:2,8-PAD")
      (libsource (lib "eagle-import") (part "MOUNT-PAD-ROUND2.8"))
    )
    (comp (ref "IC1")
      (value "LD117AS50TR")
      (footprint "eagle-import:SOT223")
      (libsource (lib "eagle-import") (part "LD117A?S50TR"))
    )
    (comp (ref "IC2")
      (value "LD117AS33TR")
      (footprint "eagle-import:SOT223")
      (libsource (lib "eagle-import") (part "LD117A?S33TR"))
    )
    (comp (ref "JP2")
      (value "BATT")
      (footprint "eagle-import:1X03_90")
      (libsource (lib "eagle-import") (part "PINHD-1X3/90"))
    )
    (comp (ref "R3")
      (value "9k1")
      (footprint "eagle-import:R0805")
      (libsource (lib "eagle-import") (part "R-EU_R0805"))
    )
    (comp (ref "R4")
      (value "1k")
      (footprint "eagle-import:R0805")
      (libsource (lib "eagle-import") (part "R-EU_R0805"))
    )
    (comp (ref "U$2")
      (value "2A")
      (footprint "eagle-import:1206")
      (libsource (lib "eagle-import") (part "SMD-FUSE"))
    )
    (comp (ref "JP6")
      (value "GPS_CONN")
      (footprint "eagle-import:1X03")
      (libsource (lib "eagle-import") (part "PINHD-1X3"))
    )
    (comp (ref "JP7")
      (value "DBG_CONN")
      (footprint "eagle-import:1X03")
      (libsource (lib "eagle-import") (part "PINHD-1X3"))
    )
    (comp (ref "JP8")
      (value "KBD_CONN")
      (footprint "eagle-import:1X03")
      (libsource (lib "eagle-import") (part "PINHD-1X3"))
    )
    (comp (ref "U4")
      (value "ADAM TECH MCSP-Q1-08-A-SG")
      (footprint "eagle-import:MICROSD-PUSH-OUT")
      (libsource (lib "eagle-import") (part "MICROSD-PUSH-OUT"))
    )
  )
  (nets
    (net (code "1") (name "+3V3") (class "Default")
      (node (ref "C10") (pin "1") (pinfunction "1_1") (pintype "passive"))
      (node (ref "C12") (pin "1") (pinfunction "1_1") (pintype "passive"))
      (node (ref "C13") (pin "1") (pinfunction "1_1") (pintype "passive"))
      (node (ref "C14") (pin "1") (pinfunction "1_1") (pintype "passive"))
      (node (ref "C15") (pin "1") (pinfunction "1_1") (pintype "passive"))
      (node (ref "C16") (pin "1") (pinfunction "1_1") (pintype "passive"))
      (node (ref "C18") (pin "1") (pinfunction "1_1") (pintype "passive"))
      (node (ref "C19") (pin "1") (pinfunction "1_1") (pintype "passive"))
      (node (ref "C24") (pin "1") (pinfunction "1_1") (pintype "passive"))
      (node (ref "C25") (pin "1") (pinfunction "1_1") (pintype "passive"))
      (node (ref "C34") (pin "1") (pinfunction "1_1") (pintype "passive"))
      (node (ref "IC2") (pin "4") (pinfunction "OUT_4") (pintype "passive"))
      (node (ref "IC3") (pin "7") (pinfunction "V+_7") (pintype "power_in"))
      (node (ref "JP3") (pin "5") (pinfunction "5_5") (pintype "passive"))
      (node (ref "JP6") (pin "1") (pinfunction "1_1") (pintype "passive"))
      (node (ref "JP8") (pin "1") (pinfunction "1_1") (pintype "passive"))
      (node (ref "L1") (pin "1") (pinfunction "1_1") (pintype "passive"))
      (node (ref "L2") (pin "1") (pinfunction "1_1") (pintype "passive"))
      (node (ref "LCHOKE") (pin "2") (pinfunction "2_2") (pintype "passive"))
      (node (ref "LED1") (pin "A") (pinfunction "A_A") (pintype "passive"))
      (node (ref "LED2") (pin "A") (pinfunction "A_A") (pintype "passive"))
      (node (ref "OS1") (pin "4") (pinfunction "VDD_4") (pintype "power_in"))
      (node (ref "R15") (pin "2") (pinfunction "2_2") (pintype "passive"))
      (node (ref "R2") (pin "1") (pinfunction "1_1") (pintype "passive"))
      (node (ref "R21") (pin "2") (pinfunction "2_2") (pintype "passive"))
      (node (ref "R22") (pin "2") (pinfunction "2_2") (pintype "passive"))
      (node (ref "R28") (pin "2") (pinfunction "2_2") (pintype "passive"))
      (node (ref "R9") (pin "1") (pinfunction "1_1") (pintype "passive"))
      (node (ref "U$1") (pin "P$1") (pinfunction "VDDIO_P$1") (pintype "power_in"))
      (node (ref "U$1") (pin "P$6") (pinfunction "VS_P$6") (pintype "power_in"))
      (node (ref "U$1") (pin "P$7") (pinfunction "~{CS}_P$7") (pintype "input"))
      (node (ref "U1") (pin "100") (pinfunction "P$100_100") (pintype "bidirectional"))
      (node (ref "U1") (pin "11") (pinfunction "P$11_11") (pintype "bidirectional"))
      (node (ref "U1") (pin "27") (pinfunction "P$27_27") (pintype "bidirectional"))
      (node (ref "U1") (pin "50") (pinfunction "P$50_50") (pintype "bidirectional"))
      (node (ref "U1") (pin "6") (pinfunction "P$6_6") (pintype "bidirectional"))
      (node (ref "U1") (pin "75") (pinfunction "P$75_75") (pintype "bidirectional"))
      (node (ref "U4") (pin "4") (pinfunction "VDD_4") (pintype "bidirectional"))
      (node (ref "U5") (pin "6") (pinfunction "VDD_6") (pintype "power_in"))
      (node (ref "U5") (pin "8") (pinfunction "VDD_8") (pintype "power_in"))
      (node (ref "U6") (pin "6") (pinfunction "VDD_6") (pintype "bidirectional"))
      (node (ref "X3") (pin "4") (pinfunction "VDD_4") (pintype "power_in"))
      (node (ref "X4") (pin "2") (pinfunction "S_2") (pintype "passive"))
    )
    (net (code "2") (name "+5V") (class "Default")
      (node (ref "C9") (pin "1") (pinfunction "1_1") (pintype "passive"))
      (node (ref "IC1") (pin "4") (pinfunction "OUT_4") (pintype "passive"))
      (node (ref "IC2") (pin "3") (pinfunction "IN_3") (pintype "input"))
    )
    (net (code "3") (name "+BATT") (class "Default")
      (node (ref "C32") (pin "1") (pinfunction "1_1") (pintype "passive"))
      (node (ref "C46") (pin "1") (pinfunction "1_1") (pintype "passive"))
      (node (ref "C47") (pin "1") (pinfunction "1_1") (pintype "passive"))
      (node (ref "C48") (pin "2") (pinfunction "2_2") (pintype "passive"))
      (node (ref "C8") (pin "+") (pinfunction "+_+") (pintype "passive"))
      (node (ref "D1") (pin "C") (pinfunction "C_C") (pintype "passive"))
      (node (ref "IC1") (pin "3") (pinfunction "IN_3") (pintype "input"))
      (node (ref "L5") (pin "1") (pinfunction "1_1") (pintype "passive"))
      (node (ref "L7") (pin "2") (pinfunction "2_2") (pintype "passive"))
      (node (ref "R14") (pin "1") (pinfunction "1_1") (pintype "passive"))
      (node (ref "R3") (pin "2") (pinfunction "2_2") (pintype "passive"))
      (node (ref "U$2") (pin "2") (pinfunction "P$2_2") (pintype "bidirectional"))
    )
    (net (code "4") (name "32M") (class "Default")
      (node (ref "U5") (pin "17") (pinfunction "XIN_17") (pintype "input"))
      (node (ref "X3") (pin "3") (pinfunction "OUT_3") (pintype "output"))
    )
    (net (code "5") (name "ADC1_0") (class "Default")
      (node (ref "IC3") (pin "6") (pinfunction "OUT_6") (pintype "output"))
      (node (ref "R7") (pin "2") (pinfunction "2_2") (pintype "passive"))
      (node (ref "U1") (pin "22") (pinfunction "P$22_22") (pintype "bidirectional"))
    )
    (net (code "6") (name "ADC2_3") (class "Default")
      (node (ref "C7") (pin "1") (pinfunction "1_1") (pintype "passive"))
      (node (ref "R3") (pin "1") (pinfunction "1_1") (pintype "passive"))
      (node (ref "R4") (pin "2") (pinfunction "2_2") (pintype "passive"))
      (node (ref "U1") (pin "25") (pinfunction "P$25_25") (pintype "bidirectional"))
    )
    (net (code "7") (name "BLIGHT_CTRL") (class "Default")
      (node (ref "Q1") (pin "1") (pinfunction "G_1") (pintype "passive"))
      (node (ref "U1") (pin "59") (pinfunction "P$59_59") (pintype "bidirectional"))
    )
    (net (code "8") (name "BOOT0") (class "Default")
      (node (ref "R1") (pin "2") (pinfunction "2_2") (pintype "passive"))
      (node (ref "U1") (pin "94") (pinfunction "P$94_94") (pintype "bidirectional"))
    )
    (net (code "9") (name "DAC_OUT") (class "Default")
      (node (ref "C26") (pin "1") (pinfunction "1_1") (pintype "passive"))
      (node (ref "U1") (pin "28") (pinfunction "P$28_28") (pintype "bidirectional"))
    )
    (net (code "10") (name "GND") (class "Default")
      (node (ref "C10") (pin "2") (pinfunction "2_2") (pintype "passive"))
      (node (ref "C12") (pin "2") (pinfunction "2_2") (pintype "passive"))
      (node (ref "C13") (pin "2") (pinfunction "2_2") (pintype "passive"))
      (node (ref "C14") (pin "2") (pinfunction "2_2") (pintype "passive"))
      (node (ref "C15") (pin "2") (pinfunction "2_2") (pintype "passive"))
      (node (ref "C16") (pin "2") (pinfunction "2_2") (pintype "passive"))
      (node (ref "C18") (pin "2") (pinfunction "2_2") (pintype "passive"))
      (node (ref "C19") (pin "2") (pinfunction "2_2") (pintype "passive"))
      (node (ref "C2") (pin "2") (pinfunction "2_2") (pintype "passive"))
      (node (ref "C20") (pin "2") (pinfunction "2_2") (pintype "passive"))
      (node (ref "C21") (pin "1") (pinfunction "1_1") (pintype "passive"))
      (node (ref "C23") (pin "2") (pinfunction "2_2") (pintype "passive"))
      (node (ref "C24") (pin "2") (pinfunction "2_2") (pintype "passive"))
      (node (ref "C25") (pin "2") (pinfunction "2_2") (pintype "passive"))
      (node (ref "C27") (pin "2") (pinfunction "2_2") (pintype "passive"))
      (node (ref "C28") (pin "1") (pinfunction "1_1") (pintype "passive"))
      (node (ref "C29") (pin "2") (pinfunction "2_2") (pintype "passive"))
      (node (ref "C30") (pin "1") (pinfunction "1_1") (pintype "passive"))
      (node (ref "C31") (pin "2") (pinfunction "2_2") (pintype "passive"))
      (node (ref "C32") (pin "2") (pinfunction "2_2") (pintype "passive"))
      (node (ref "C33") (pin "2") (pinfunction "2_2") (pintype "passive"))
      (node (ref "C34") (pin "2") (pinfunction "2_2") (pintype "passive"))
      (node (ref "C35") (pin "2") (pinfunction "2_2") (pintype "passive"))
      (node (ref "C37") (pin "2") (pinfunction "2_2") (pintype "passive"))
      (node (ref "C38") (pin "2") (pinfunction "2_2") (pintype "passive"))
      (node (ref "C39") (pin "2") (pinfunction "2_2") (pintype "passive"))
      (node (ref "C4") (pin "2") (pinfunction "2_2") (pintype "passive"))
      (node (ref "C40") (pin "1") (pinfunction "1_1") (pintype "passive"))
      (node (ref "C41") (pin "2") (pinfunction "2_2") (pintype "passive"))
      (node (ref "C42") (pin "2") (pinfunction "2_2") (pintype "passive"))
      (node (ref "C43") (pin "1") (pinfunction "1_1") (pintype "passive"))
      (node (ref "C45") (pin "1") (pinfunction "1_1") (pintype "passive"))
      (node (ref "C46") (pin "2") (pinfunction "2_2") (pintype "passive"))
      (node (ref "C47") (pin "2") (pinfunction "2_2") (pintype "passive"))
      (node (ref "C48") (pin "1") (pinfunction "1_1") (pintype "passive"))
      (node (ref "C5") (pin "2") (pinfunction "2_2") (pintype "passive"))
      (node (ref "C6") (pin "1") (pinfunction "1_1") (pintype "passive"))
      (node (ref "C7") (pin "2") (pinfunction "2_2") (pintype "passive"))
      (node (ref "C8") (pin "-") (pinfunction "-_-") (pintype "passive"))
      (node (ref "C9") (pin "2") (pinfunction "2_2") (pintype "passive"))
      (node (ref "CM") (pin "2") (pinfunction "2_2") (pintype "passive"))
      (node (ref "CM1") (pin "2") (pinfunction "2_2") (pintype "passive"))
      (node (ref "CM2") (pin "2") (pinfunction "2_2") (pintype "passive"))
      (node (ref "CM3") (pin "2") (pinfunction "2_2") (pintype "passive"))
      (node (ref "CR1") (pin "2") (pinfunction "2_2") (pintype "passive"))
      (node (ref "C_ACG") (pin "2") (pinfunction "2_2") (pintype "passive"))
      (node (ref "D1") (pin "A") (pinfunction "A_A") (pintype "passive"))
      (node (ref "H1") (pin "B2,8") (pinfunction "MOUNT_B2,8") (pintype "passive"))
      (node (ref "H2") (pin "B2,8") (pinfunction "MOUNT_B2,8") (pintype "passive"))
      (node (ref "H3") (pin "B2,8") (pinfunction "MOUNT_B2,8") (pintype "passive"))
      (node (ref "H4") (pin "B2,8") (pinfunction "MOUNT_B2,8") (pintype "passive"))
      (node (ref "IC1") (pin "1") (pinfunction "ADJ_1") (pintype "input"))
      (node (ref "IC2") (pin "1") (pinfunction "ADJ_1") (pintype "input"))
      (node (ref "IC3") (pin "4") (pinfunction "V-_4") (pintype "power_in"))
      (node (ref "JP2") (pin "3") (pinfunction "3_3") (pintype "passive"))
      (node (ref "JP3") (pin "1") (pinfunction "1_1") (pintype "passive"))
      (node (ref "JP5") (pin "2") (pinfunction "2_2") (pintype "passive"))
      (node (ref "JP6") (pin "3") (pinfunction "3_3") (pintype "passive"))
      (node (ref "JP7") (pin "3") (pinfunction "3_3") (pintype "passive"))
      (node (ref "JP8") (pin "3") (pinfunction "3_3") (pintype "passive"))
      (node (ref "OS1") (pin "2") (pinfunction "VSS_2") (pintype "power_in"))
      (node (ref "Q1") (pin "2") (pinfunction "S_2") (pintype "passive"))
      (node (ref "R1") (pin "1") (pinfunction "1_1") (pintype "passive"))
      (node (ref "R12") (pin "2") (pinfunction "2_2") (pintype "passive"))
      (node (ref "R13") (pin "2") (pinfunction "2_2") (pintype "passive"))
      (node (ref "R27") (pin "1") (pinfunction "1_1") (pintype "passive"))
      (node (ref "R4") (pin "1") (pinfunction "1_1") (pintype "passive"))
      (node (ref "S1") (pin "2") (pinfunction "S_2") (pintype "passive"))
      (node (ref "T3") (pin "S") (pinfunction "S_S") (pintype "passive"))
      (node (ref "U$1") (pin "P$12") (pinfunction "MISO_P$12") (pintype "output"))
      (node (ref "U$1") (pin "P$2") (pinfunction "GND$1_P$2") (pintype "power_in"))
      (node (ref "U$1") (pin "P$4") (pinfunction "GND$2_P$4") (pintype "power_in"))
      (node (ref "U$1") (pin "P$5") (pinfunction "GND$3_P$5") (pintype "power_in"))
      (node (ref "U1") (pin "10") (pinfunction "P$10_10") (pintype "bidirectional"))
      (node (ref "U1") (pin "19") (pinfunction "P$19_19") (pintype "bidirectional"))
      (node (ref "U1") (pin "26") (pinfunction "P$26_26") (pintype "bidirectional"))
      (node (ref "U1") (pin "49") (pinfunction "P$49_49") (pintype "bidirectional"))
      (node (ref "U1") (pin "74") (pinfunction "P$74_74") (pintype "bidirectional"))
      (node (ref "U1") (pin "99") (pinfunction "P$99_99") (pintype "bidirectional"))
      (node (ref "U3") (pin "6") (pinfunction "GND_6") (pintype "bidirectional"))
      (node (ref "U4") (pin "6") (pinfunction "VSS_6") (pintype "bidirectional"))
      (node (ref "U4") (pin "G1") (pinfunction "VSS_G1") (pintype "bidirectional"))
      (node (ref "U4") (pin "G2") (pinfunction "VSS_G2") (pintype "bidirectional"))
      (node (ref "U4") (pin "G3") (pinfunction "VSS_G3") (pintype "bidirectional"))
      (node (ref "U4") (pin "G4") (pinfunction "VSS_G4") (pintype "bidirectional"))
      (node (ref "U5") (pin "18") (pinfunction "GND_18") (pintype "power_in"))
      (node (ref "U5") (pin "21") (pinfunction "GND_21") (pintype "power_in"))
      (node (ref "U6") (pin "2") (pinfunction "GND1_2") (pintype "bidirectional"))
      (node (ref "U6") (pin "7") (pinfunction "GND2_7") (pintype "bidirectional"))
      (node (ref "X2") (pin "G@1") (pinfunction "2_G@1") (pintype "passive"))
      (node (ref "X2") (pin "G@2") (pinfunction "2_G@2") (pintype "passive"))
      (node (ref "X2") (pin "G@3") (pinfunction "2_G@3") (pintype "passive"))
      (node (ref "X2") (pin "G@4") (pinfunction "2_G@4") (pintype "passive"))
      (node (ref "X3") (pin "2") (pinfunction "GND_2") (pintype "power_in"))
      (node (ref "X4") (pin "1") (pinfunction "S_1") (pintype "passive"))
    )
    (net (code "11") (name "I2C1_SCL") (class "Default")
      (node (ref "R22") (pin "1") (pinfunction "1_1") (pintype "passive"))
      (node (ref "U$1") (pin "P$14") (pinfunction "SCLK_P$14") (pintype "input"))
      (node (ref "U1") (pin "92") (pinfunction "P$92_92") (pintype "bidirectional"))
    )
    (net (code "12") (name "I2C1_SDA") (class "Default")
      (node (ref "R21") (pin "1") (pinfunction "1_1") (pintype "passive"))
      (node (ref "U$1") (pin "P$13") (pinfunction "MOSI_P$13") (pintype "input"))
      (node (ref "U1") (pin "93") (pinfunction "P$93_93") (pintype "bidirectional"))
    )
    (net (code "13") (name "LED_GRN") (class "Default")
      (node (ref "R18") (pin "1") (pinfunction "1_1") (pintype "passive"))
      (node (ref "U1") (pin "81") (pinfunction "P$81_81") (pintype "bidirectional"))
    )
    (net (code "14") (name "LED_RED") (class "Default")
      (node (ref "R17") (pin "1") (pinfunction "1_1") (pintype "passive"))
      (node (ref "U1") (pin "82") (pinfunction "P$82_82") (pintype "bidirectional"))
    )
    (net (code "15") (name "MIC_AMP_IN") (class "Default")
      (node (ref "C22") (pin "2") (pinfunction "2_2") (pintype "passive"))
      (node (ref "JP5") (pin "1") (pinfunction "1_1") (pintype "passive"))
      (node (ref "R16") (pin "2") (pinfunction "2_2") (pintype "passive"))
    )
    (net (code "16") (name "NRST") (class "Default")
      (node (ref "JP3") (pin "2") (pinfunction "2_2") (pintype "passive"))
      (node (ref "R2") (pin "2") (pinfunction "2_2") (pintype "passive"))
      (node (ref "U1") (pin "14") (pinfunction "P$14_14") (pintype "bidirectional"))
    )
    (net (code "17") (name "Net-(C0-Pad2)") (class "Default")
      (node (ref "C0") (pin "2") (pinfunction "2_2") (pintype "passive"))
      (node (ref "L0") (pin "1") (pinfunction "1_1") (pintype "passive"))
    )
    (net (code "18") (name "Net-(C20-Pad1)") (class "Default")
      (node (ref "C20") (pin "1") (pinfunction "1_1") (pintype "passive"))
      (node (ref "R8") (pin "1") (pinfunction "1_1") (pintype "passive"))
    )
    (net (code "19") (name "Net-(C22-Pad1)") (class "Default")
      (node (ref "C22") (pin "1") (pinfunction "1_1") (pintype "passive"))
      (node (ref "R10") (pin "1") (pinfunction "1_1") (pintype "passive"))
      (node (ref "R11") (pin "1") (pinfunction "1_1") (pintype "passive"))
    )
    (net (code "20") (name "Net-(C23-Pad1)") (class "Default")
      (node (ref "C23") (pin "1") (pinfunction "1_1") (pintype "passive"))
      (node (ref "R11") (pin "2") (pinfunction "2_2") (pintype "passive"))
      (node (ref "R12") (pin "1") (pinfunction "1_1") (pintype "passive"))
      (node (ref "R9") (pin "2") (pinfunction "2_2") (pintype "passive"))
    )
    (net (code "21") (name "Net-(C26-Pad2)") (class "Default")
      (node (ref "C26") (pin "2") (pinfunction "2_2") (pintype "passive"))
      (node (ref "R19") (pin "2") (pinfunction "2_2") (pintype "passive"))
      (node (ref "R25") (pin "2") (pinfunction "2_2") (pintype "passive"))
    )
    (net (code "22") (name "Net-(C27-Pad1)") (class "Default")
      (node (ref "C27") (pin "1") (pinfunction "1_1") (pintype "passive"))
      (node (ref "C35") (pin "1") (pinfunction "1_1") (pintype "passive"))
      (node (ref "L3") (pin "2") (pinfunction "2_2") (pintype "passive"))
      (node (ref "LM2") (pin "2") (pinfunction "2_2") (pintype "passive"))
    )
    (net (code "23") (name "Net-(C28-Pad2)") (class "Default")
      (node (ref "C28") (pin "2") (pinfunction "2_2") (pintype "passive"))
      (node (ref "R15") (pin "1") (pinfunction "1_1") (pintype "passive"))
      (node (ref "R16") (pin "1") (pinfunction "1_1") (pintype "passive"))
    )
    (net (code "24") (name "Net-(C38-Pad1)") (class "Default")
      (node (ref "C38") (pin "1") (pinfunction "1_1") (pintype "passive"))
      (node (ref "L4") (pin "1") (pinfunction "1_1") (pintype "passive"))
      (node (ref "L7") (pin "1") (pinfunction "1_1") (pintype "passive"))
      (node (ref "T3") (pin "D") (pinfunction "D_D") (pintype "passive"))
    )
    (net (code "25") (name "Net-(C39-Pad1)") (class "Default")
      (node (ref "C39") (pin "1") (pinfunction "1_1") (pintype "passive"))
      (node (ref "C40") (pin "2") (pinfunction "2_2") (pintype "passive"))
      (node (ref "L4") (pin "2") (pinfunction "2_2") (pintype "passive"))
      (node (ref "L6") (pin "1") (pinfunction "1_1") (pintype "passive"))
    )
    (net (code "26") (name "Net-(C42-Pad1)") (class "Default")
      (node (ref "C42") (pin "1") (pinfunction "1_1") (pintype "passive"))
      (node (ref "C43") (pin "2") (pinfunction "2_2") (pintype "passive"))
      (node (ref "CC3") (pin "1") (pinfunction "1_1") (pintype "passive"))
      (node (ref "L6") (pin "2") (pinfunction "2_2") (pintype "passive"))
    )
    (net (code "27") (name "Net-(CC1-Pad1)") (class "Default")
      (node (ref "CC1") (pin "1") (pinfunction "1_1") (pintype "passive"))
      (node (ref "CR2") (pin "2") (pinfunction "2_2") (pintype "passive"))
      (node (ref "LR2") (pin "2") (pinfunction "2_2") (pintype "passive"))
    )
    (net (code "28") (name "Net-(CC2-Pad2)") (class "Default")
      (node (ref "CC2") (pin "2") (pinfunction "2_2") (pintype "passive"))
      (node (ref "CM2") (pin "1") (pinfunction "1_1") (pintype "passive"))
      (node (ref "LM3") (pin "1") (pinfunction "1_1") (pintype "passive"))
    )
    (net (code "29") (name "Net-(CM-Pad1)") (class "Default")
      (node (ref "CM") (pin "1") (pinfunction "1_1") (pintype "passive"))
      (node (ref "L0") (pin "2") (pinfunction "2_2") (pintype "passive"))
      (node (ref "LM1") (pin "1") (pinfunction "1_1") (pintype "passive"))
    )
    (net (code "30") (name "Net-(CM1-Pad1)") (class "Default")
      (node (ref "CM1") (pin "1") (pinfunction "1_1") (pintype "passive"))
      (node (ref "LM1") (pin "2") (pinfunction "2_2") (pintype "passive"))
      (node (ref "LM2") (pin "1") (pinfunction "1_1") (pintype "passive"))
    )
    (net (code "31") (name "Net-(CM3-Pad1)") (class "Default")
      (node (ref "CM3") (pin "1") (pinfunction "1_1") (pintype "passive"))
      (node (ref "LM3") (pin "2") (pinfunction "2_2") (pintype "passive"))
      (node (ref "X2") (pin "1") (pinfunction "1_1") (pintype "passive"))
    )
    (net (code "32") (name "Net-(IC3-+IN)") (class "Default")
      (node (ref "C21") (pin "2") (pinfunction "2_2") (pintype "passive"))
      (node (ref "IC3") (pin "3") (pinfunction "+IN_3") (pintype "input"))
      (node (ref "R10") (pin "2") (pinfunction "2_2") (pintype "passive"))
    )
    (net (code "33") (name "Net-(IC3--IN)") (class "Default")
      (node (ref "IC3") (pin "2") (pinfunction "-IN_2") (pintype "input"))
      (node (ref "R7") (pin "1") (pinfunction "1_1") (pintype "passive"))
      (node (ref "R8") (pin "2") (pinfunction "2_2") (pintype "passive"))
    )
    (net (code "34") (name "Net-(L3-Pad1)") (class "Default")
      (node (ref "L3") (pin "1") (pinfunction "1_1") (pintype "passive"))
      (node (ref "R26") (pin "1") (pinfunction "1_1") (pintype "passive"))
      (node (ref "T3") (pin "G") (pinfunction "G_G") (pintype "passive"))
    )
    (net (code "35") (name "Net-(LED1-PadC)") (class "Default")
      (node (ref "LED1") (pin "C") (pinfunction "C_C") (pintype "passive"))
      (node (ref "R17") (pin "2") (pinfunction "2_2") (pintype "passive"))
    )
    (net (code "36") (name "Net-(LED2-PadC)") (class "Default")
      (node (ref "LED2") (pin "C") (pinfunction "C_C") (pintype "passive"))
      (node (ref "R18") (pin "2") (pinfunction "2_2") (pintype "passive"))
    )
    (net (code "37") (name "Net-(R29-A)") (class "Default")
      (node (ref "R27") (pin "2") (pinfunction "2_2") (pintype "passive"))
      (node (ref "R29") (pin "1") (pinfunction "A_1") (pintype "passive"))
    )
    (net (code "38") (name "Net-(R29-E)") (class "Default")
      (node (ref "R28") (pin "1") (pinfunction "1_1") (pintype "passive"))
      (node (ref "R29") (pin "3") (pinfunction "E_3") (pintype "passive"))
    )
    (net (code "39") (name "Net-(U$2-P$1)") (class "Default")
      (node (ref "JP2") (pin "1") (pinfunction "1_1") (pintype "passive"))
      (node (ref "U$2") (pin "1") (pinfunction "P$1_1") (pintype "bidirectional"))
    )
    (net (code "40") (name "Net-(U1-P$39)") (class "Default")
      (node (ref "TP1") (pin "TP") (pinfunction "TP_TP") (pintype "input"))
      (node (ref "U1") (pin "39") (pinfunction "P$39_39") (pintype "bidirectional"))
    )
    (net (code "41") (name "Net-(U1-P$40)") (class "Default")
      (node (ref "TP2") (pin "TP") (pinfunction "TP_TP") (pintype "input"))
      (node (ref "U1") (pin "40") (pinfunction "P$40_40") (pintype "bidirectional"))
    )
    (net (code "42") (name "Net-(U1-P$48)") (class "Default")
      (node (ref "C5") (pin "1") (pinfunction "1_1") (pintype "passive"))
      (node (ref "U1") (pin "48") (pinfunction "P$48_48") (pintype "bidirectional"))
    )
    (net (code "43") (name "Net-(U1-P$73)") (class "Default")
      (node (ref "C6") (pin "2") (pinfunction "2_2") (pintype "passive"))
      (node (ref "U1") (pin "73") (pinfunction "P$73_73") (pintype "bidirectional"))
    )
    (net (code "44") (name "Net-(U3-IN1+)") (class "Default")
      (node (ref "C30") (pin "2") (pinfunction "2_2") (pintype "passive"))
      (node (ref "R13") (pin "1") (pinfunction "1_1") (pintype "passive"))
      (node (ref "R14") (pin "2") (pinfunction "2_2") (pintype "passive"))
      (node (ref "R25") (pin "1") (pinfunction "1_1") (pintype "passive"))
      (node (ref "U3") (pin "12") (pinfunction "IN2+_12") (pintype "bidirectional"))
      (node (ref "U3") (pin "13") (pinfunction "IN1+_13") (pintype "bidirectional"))
    )
    (net (code "45") (name "Net-(U3-IN1-)") (class "Default")
      (node (ref "R19") (pin "1") (pinfunction "1_1") (pintype "passive"))
      (node (ref "R20") (pin "1") (pinfunction "1_1") (pintype "passive"))
      (node (ref "U3") (pin "14") (pinfunction "IN1-_14") (pintype "bidirectional"))
    )
    (net (code "46") (name "Net-(U3-IN2-)") (class "Default")
      (node (ref "R23") (pin "1") (pinfunction "1_1") (pintype "passive"))
      (node (ref "R24") (pin "1") (pinfunction "1_1") (pintype "passive"))
      (node (ref "U3") (pin "11") (pinfunction "IN2-_11") (pintype "bidirectional"))
    )
    (net (code "47") (name "Net-(U6-ACG)") (class "Default")
      (node (ref "C_ACG") (pin "1") (pinfunction "1_1") (pintype "passive"))
      (node (ref "U6") (pin "4") (pinfunction "ACG_4") (pintype "bidirectional"))
    )
    (net (code "48") (name "Net-(U6-RFC)") (class "Default")
      (node (ref "CC2") (pin "1") (pinfunction "1_1") (pintype "passive"))
      (node (ref "U6") (pin "8") (pinfunction "RFC_8") (pintype "bidirectional"))
    )
    (net (code "49") (name "Net-(U6-RX)") (class "Default")
      (node (ref "CC1") (pin "2") (pinfunction "2_2") (pintype "passive"))
      (node (ref "U6") (pin "5") (pinfunction "RX_5") (pintype "bidirectional"))
    )
    (net (code "50") (name "Net-(U6-TX)") (class "Default")
      (node (ref "CC3") (pin "2") (pinfunction "2_2") (pintype "passive"))
      (node (ref "U6") (pin "1") (pinfunction "TX_1") (pintype "bidirectional"))
    )
    (net (code "51") (name "OSC_IN") (class "Default")
      (node (ref "OS1") (pin "3") (pinfunction "OUT_3") (pintype "output"))
      (node (ref "U1") (pin "12") (pinfunction "P$12_12") (pintype "bidirectional"))
    )
    (net (code "52") (name "PA_BIAS") (class "Default")
      (node (ref "C37") (pin "1") (pinfunction "1_1") (pintype "passive"))
      (node (ref "C41") (pin "1") (pinfunction "1_1") (pintype "passive"))
      (node (ref "C45") (pin "2") (pinfunction "2_2") (pintype "passive"))
      (node (ref "R26") (pin "2") (pinfunction "2_2") (pintype "passive"))
      (node (ref "R29") (pin "2") (pinfunction "S_2") (pintype "passive"))
    )
    (net (code "53") (name "PA_SUPP") (class "Default")
      (node (ref "C29") (pin "1") (pinfunction "1_1") (pintype "passive"))
      (node (ref "C31") (pin "1") (pinfunction "1_1") (pintype "passive"))
      (node (ref "L5") (pin "2") (pinfunction "2_2") (pintype "passive"))
      (node (ref "U3") (pin "4") (pinfunction "SUPP_4") (pintype "bidirectional"))
    )
    (net (code "54") (name "PTT_INT") (class "Default")
      (node (ref "C33") (pin "1") (pinfunction "1_1") (pintype "passive"))
      (node (ref "S1") (pin "1") (pinfunction "P_1") (pintype "passive"))
      (node (ref "U1") (pin "97") (pinfunction "P$97_97") (pintype "bidirectional"))
    )
    (net (code "55") (name "RXN") (class "Default")
      (node (ref "CR1") (pin "1") (pinfunction "1_1") (pintype "passive"))
      (node (ref "LR1") (pin "1") (pinfunction "1_1") (pintype "passive"))
      (node (ref "LR2") (pin "1") (pinfunction "1_1") (pintype "passive"))
      (node (ref "U5") (pin "3") (pinfunction "RXN_3") (pintype "input"))
    )
    (net (code "56") (name "RXP") (class "Default")
      (node (ref "CR2") (pin "1") (pinfunction "1_1") (pintype "passive"))
      (node (ref "LR1") (pin "2") (pinfunction "2_2") (pintype "passive"))
      (node (ref "U5") (pin "2") (pinfunction "RXP_2") (pintype "input"))
    )
    (net (code "57") (name "SD_CLK") (class "Default")
      (node (ref "U1") (pin "80") (pinfunction "P$80_80") (pintype "bidirectional"))
      (node (ref "U4") (pin "5") (pinfunction "CLK_5") (pintype "bidirectional"))
    )
    (net (code "58") (name "SD_CMD") (class "Default")
      (node (ref "U1") (pin "83") (pinfunction "P$83_83") (pintype "bidirectional"))
      (node (ref "U4") (pin "3") (pinfunction "CMD_DIN_3") (pintype "bidirectional"))
    )
    (net (code "59") (name "SD_D0") (class "Default")
      (node (ref "U1") (pin "65") (pinfunction "P$65_65") (pintype "bidirectional"))
      (node (ref "U4") (pin "7") (pinfunction "DAT0_DO_7") (pintype "bidirectional"))
    )
    (net (code "60") (name "SD_D1") (class "Default")
      (node (ref "U1") (pin "66") (pinfunction "P$66_66") (pintype "bidirectional"))
      (node (ref "U4") (pin "8") (pinfunction "DAT1_8") (pintype "bidirectional"))
    )
    (net (code "61") (name "SD_D2") (class "Default")
      (node (ref "U1") (pin "78") (pinfunction "P$78_78") (pintype "bidirectional"))
      (node (ref "U4") (pin "1") (pinfunction "DAT2_1") (pintype "bidirectional"))
    )
    (net (code "62") (name "SD_D3") (class "Default")
      (node (ref "U1") (pin "79") (pinfunction "P$79_79") (pintype "bidirectional"))
      (node (ref "U4") (pin "2") (pinfunction "CD_DAT3_CS_2") (pintype "bidirectional"))
    )
    (net (code "63") (name "SPI1_CS") (class "Default")
      (node (ref "U1") (pin "32") (pinfunction "P$32_32") (pintype "bidirectional"))
      (node (ref "X4") (pin "6") (pinfunction "S_6") (pintype "passive"))
    )
    (net (code "64") (name "SPI1_MISO") (class "Default")
      (node (ref "U1") (pin "30") (pinfunction "P$30_30") (pintype "bidirectional"))
    )
    (net (code "65") (name "SPI1_MOSI") (class "Default")
      (node (ref "U1") (pin "31") (pinfunction "P$31_31") (pintype "bidirectional"))
      (node (ref "X4") (pin "5") (pinfunction "S_5") (pintype "passive"))
    )
    (net (code "66") (name "SPI1_SCK") (class "Default")
      (node (ref "U1") (pin "29") (pinfunction "P$29_29") (pintype "bidirectional"))
      (node (ref "X4") (pin "4") (pinfunction "S_4") (pintype "passive"))
    )
    (net (code "67") (name "SPI2_CS") (class "Default")
      (node (ref "U1") (pin "55") (pinfunction "P$55_55") (pintype "bidirectional"))
      (node (ref "U5") (pin "15") (pinfunction "NSEL_15") (pintype "input"))
    )
    (net (code "68") (name "SPI2_MISO") (class "Default")
      (node (ref "U1") (pin "53") (pinfunction "P$53_53") (pintype "bidirectional"))
      (node (ref "U5") (pin "13") (pinfunction "SDO_13") (pintype "output"))
    )
    (net (code "69") (name "SPI2_MOSI") (class "Default")
      (node (ref "U1") (pin "54") (pinfunction "P$54_54") (pintype "bidirectional"))
      (node (ref "U5") (pin "14") (pinfunction "SDI_14") (pintype "input"))
    )
    (net (code "70") (name "SPI2_SCK") (class "Default")
      (node (ref "U1") (pin "52") (pinfunction "P$52_52") (pintype "bidirectional"))
      (node (ref "U5") (pin "12") (pinfunction "SCLK_12") (pintype "input"))
    )
    (net (code "71") (name "SPK_N") (class "Default")
      (node (ref "JP4") (pin "2") (pinfunction "2_2") (pintype "passive"))
      (node (ref "R20") (pin "2") (pinfunction "2_2") (pintype "passive"))
      (node (ref "R24") (pin "2") (pinfunction "2_2") (pintype "passive"))
      (node (ref "U3") (pin "3") (pinfunction "OUT1_3") (pintype "bidirectional"))
    )
    (net (code "72") (name "SPK_P") (class "Default")
      (node (ref "JP4") (pin "1") (pinfunction "1_1") (pintype "passive"))
      (node (ref "R23") (pin "2") (pinfunction "2_2") (pintype "passive"))
      (node (ref "U3") (pin "5") (pinfunction "OUT2_5") (pintype "bidirectional"))
    )
    (net (code "73") (name "SWCLK") (class "Default")
      (node (ref "JP3") (pin "3") (pinfunction "3_3") (pintype "passive"))
      (node (ref "U1") (pin "76") (pinfunction "P$76_76") (pintype "bidirectional"))
    )
    (net (code "74") (name "SWDIO") (class "Default")
      (node (ref "JP3") (pin "4") (pinfunction "4_4") (pintype "passive"))
      (node (ref "U1") (pin "72") (pinfunction "P$72_72") (pintype "bidirectional"))
    )
    (net (code "75") (name "TFT_A0") (class "Default")
      (node (ref "U1") (pin "63") (pinfunction "P$63_63") (pintype "bidirectional"))
      (node (ref "X4") (pin "3") (pinfunction "S_3") (pintype "passive"))
    )
    (net (code "76") (name "TFT_LED") (class "Default")
      (node (ref "Q1") (pin "3") (pinfunction "D_3") (pintype "passive"))
      (node (ref "X4") (pin "8") (pinfunction "S_8") (pintype "passive"))
    )
    (net (code "77") (name "TFT_RST") (class "Default")
      (node (ref "U1") (pin "64") (pinfunction "P$64_64") (pintype "bidirectional"))
      (node (ref "X4") (pin "7") (pinfunction "S_7") (pintype "passive"))
    )
    (net (code "78") (name "TRX_NIRQ") (class "Default")
      (node (ref "U1") (pin "35") (pinfunction "P$35_35") (pintype "bidirectional"))
      (node (ref "U5") (pin "11") (pinfunction "NIRQ_11") (pintype "output"))
    )
    (net (code "79") (name "TRX_SDN") (class "Default")
      (node (ref "U1") (pin "34") (pinfunction "P$34_34") (pintype "bidirectional"))
      (node (ref "U5") (pin "1") (pinfunction "SDN_1") (pintype "input"))
    )
    (net (code "80") (name "TRX_SW") (class "Default")
      (node (ref "U1") (pin "5") (pinfunction "P$5_5") (pintype "bidirectional"))
      (node (ref "U6") (pin "3") (pinfunction "VCTL_3") (pintype "bidirectional"))
    )
    (net (code "81") (name "TX") (class "Default")
      (node (ref "C0") (pin "1") (pinfunction "1_1") (pintype "passive"))
      (node (ref "LCHOKE") (pin "1") (pinfunction "1_1") (pintype "passive"))
      (node (ref "U5") (pin "4") (pinfunction "TX_4") (pintype "output"))
    )
    (net (code "82") (name "USART1_RX") (class "Default")
      (node (ref "JP6") (pin "2") (pinfunction "2_2") (pintype "passive"))
      (node (ref "U1") (pin "69") (pinfunction "P$69_69") (pintype "bidirectional"))
    )
    (net (code "83") (name "USART1_TX") (class "Default")
      (node (ref "U1") (pin "68") (pinfunction "P$68_68") (pintype "bidirectional"))
    )
    (net (code "84") (name "USART2_RX") (class "Default")
      (node (ref "JP7") (pin "2") (pinfunction "2_2") (pintype "passive"))
      (node (ref "U1") (pin "87") (pinfunction "P$87_87") (pintype "bidirectional"))
    )
    (net (code "85") (name "USART2_TX") (class "Default")
      (node (ref "JP7") (pin "1") (pinfunction "1_1") (pintype "passive"))
      (node (ref "U1") (pin "86") (pinfunction "P$86_86") (pintype "bidirectional"))
    )
    (net (code "86") (name "USART3_RX") (class "Default")
      (node (ref "JP8") (pin "2") (pinfunction "2_2") (pintype "passive"))
      (node (ref "U1") (pin "47") (pinfunction "P$47_47") (pintype "bidirectional"))
    )
    (net (code "87") (name "USART3_TX") (class "Default")
      (node (ref "U1") (pin "46") (pinfunction "P$46_46") (pintype "bidirectional"))
    )
    (net (code "88") (name "VDDA") (class "Default")
      (node (ref "C2") (pin "1") (pinfunction "1_1") (pintype "passive"))
      (node (ref "L2") (pin "2") (pinfunction "2_2") (pintype "passive"))
      (node (ref "U1") (pin "21") (pinfunction "P$21_21") (pintype "bidirectional"))
    )
    (net (code "89") (name "VREF") (class "Default")
      (node (ref "C4") (pin "1") (pinfunction "1_1") (pintype "passive"))
      (node (ref "L1") (pin "2") (pinfunction "2_2") (pintype "passive"))
      (node (ref "U1") (pin "20") (pinfunction "P$20_20") (pintype "bidirectional"))
    )
    (net (code "90") (name "unconnected-(JP2-Pad2)") (class "Default")
      (node (ref "JP2") (pin "2") (pinfunction "2_2") (pintype "passive"))
    )
    (net (code "91") (name "unconnected-(OS1-CON-Pad1)") (class "Default")
      (node (ref "OS1") (pin "1") (pinfunction "CON_1") (pintype "input"))
    )
    (net (code "92") (name "unconnected-(U$1-INT1-PadP$8)") (class "Default")
      (node (ref "U$1") (pin "P$8") (pinfunction "INT1_P$8") (pintype "output"))
    )
    (net (code "93") (name "unconnected-(U$1-INT2-PadP$9)") (class "Default")
      (node (ref "U$1") (pin "P$9") (pinfunction "INT2_P$9") (pintype "output"))
    )
    (net (code "94") (name "unconnected-(U$1-NC-PadP$10)") (class "Default")
      (node (ref "U$1") (pin "P$10") (pinfunction "NC_P$10") (pintype "bidirectional"))
    )
    (net (code "95") (name "unconnected-(U$1-RESERVED$1-PadP$3)") (class "Default")
      (node (ref "U$1") (pin "P$3") (pinfunction "RESERVED$1_P$3") (pintype "bidirectional"))
    )
    (net (code "96") (name "unconnected-(U$1-RESERVED$2-PadP$11)") (class "Default")
      (node (ref "U$1") (pin "P$11") (pinfunction "RESERVED$2_P$11") (pintype "bidirectional"))
    )
    (net (code "97") (name "unconnected-(U1-P$1-Pad1)") (class "Default")
      (node (ref "U1") (pin "1") (pinfunction "P$1_1") (pintype "bidirectional"))
    )
    (net (code "98") (name "unconnected-(U1-P$2-Pad2)") (class "Default")
      (node (ref "U1") (pin "2") (pinfunction "P$2_2") (pintype "bidirectional"))
    )
    (net (code "99") (name "unconnected-(U1-P$3-Pad3)") (class "Default")
      (node (ref "U1") (pin "3") (pinfunction "P$3_3") (pintype "bidirectional"))
    )
    (net (code "100") (name "unconnected-(U1-P$4-Pad4)") (class "Default")
      (node (ref "U1") (pin "4") (pinfunction "P$4_4") (pintype "bidirectional"))
    )
    (net (code "101") (name "unconnected-(U1-P$7-Pad7)") (class "Default")
      (node (ref "U1") (pin "7") (pinfunction "P$7_7") (pintype "bidirectional"))
    )
    (net (code "102") (name "unconnected-(U1-P$8-Pad8)") (class "Default")
      (node (ref "U1") (pin "8") (pinfunction "P$8_8") (pintype "bidirectional"))
    )
    (net (code "103") (name "unconnected-(U1-P$9-Pad9)") (class "Default")
      (node (ref "U1") (pin "9") (pinfunction "P$9_9") (pintype "bidirectional"))
    )
    (net (code "104") (name "unconnected-(U1-P$13-Pad13)") (class "Default")
      (node (ref "U1") (pin "13") (pinfunction "P$13_13") (pintype "bidirectional"))
    )
    (net (code "105") (name "unconnected-(U1-P$15-Pad15)") (class "Default")
      (node (ref "U1") (pin "15") (pinfunction "P$15_15") (pintype "bidirectional"))
    )
    (net (code "106") (name "unconnected-(U1-P$16-Pad16)") (class "Default")
      (node (ref "U1") (pin "16") (pinfunction "P$16_16") (pintype "bidirectional"))
    )
    (net (code "107") (name "unconnected-(U1-P$17-Pad17)") (class "Default")
      (node (ref "U1") (pin "17") (pinfunction "P$17_17") (pintype "bidirectional"))
    )
    (net (code "108") (name "unconnected-(U1-P$18-Pad18)") (class "Default")
      (node (ref "U1") (pin "18") (pinfunction "P$18_18") (pintype "bidirectional"))
    )
    (net (code "109") (name "unconnected-(U1-P$23-Pad23)") (class "Default")
      (node (ref "U1") (pin "23") (pinfunction "P$23_23") (pintype "bidirectional"))
    )
    (net (code "110") (name "unconnected-(U1-P$24-Pad24)") (class "Default")
      (node (ref "U1") (pin "24") (pinfunction "P$24_24") (pintype "bidirectional"))
    )
    (net (code "111") (name "unconnected-(U1-P$33-Pad33)") (class "Default")
      (node (ref "U1") (pin "33") (pinfunction "P$33_33") (pintype "bidirectional"))
    )
    (net (code "112") (name "unconnected-(U1-P$36-Pad36)") (class "Default")
      (node (ref "U1") (pin "36") (pinfunction "P$36_36") (pintype "bidirectional"))
    )
    (net (code "113") (name "unconnected-(U1-P$37-Pad37)") (class "Default")
      (node (ref "U1") (pin "37") (pinfunction "P$37_37") (pintype "bidirectional"))
    )
    (net (code "114") (name "unconnected-(U1-P$38-Pad38)") (class "Default")
      (node (ref "U1") (pin "38") (pinfunction "P$38_38") (pintype "bidirectional"))
    )
    (net (code "115") (name "unconnected-(U1-P$41-Pad41)") (class "Default")
      (node (ref "U1") (pin "41") (pinfunction "P$41_41") (pintype "bidirectional"))
    )
    (net (code "116") (name "unconnected-(U1-P$42-Pad42)") (class "Default")
      (node (ref "U1") (pin "42") (pinfunction "P$42_42") (pintype "bidirectional"))
    )
    (net (code "117") (name "unconnected-(U1-P$43-Pad43)") (class "Default")
      (node (ref "U1") (pin "43") (pinfunction "P$43_43") (pintype "bidirectional"))
    )
    (net (code "118") (name "unconnected-(U1-P$44-Pad44)") (class "Default")
      (node (ref "U1") (pin "44") (pinfunction "P$44_44") (pintype "bidirectional"))
    )
    (net (code "119") (name "unconnected-(U1-P$45-Pad45)") (class "Default")
      (node (ref "U1") (pin "45") (pinfunction "P$45_45") (pintype "bidirectional"))
    )
    (net (code "120") (name "unconnected-(U1-P$51-Pad51)") (class "Default")
      (node (ref "U1") (pin "51") (pinfunction "P$51_51") (pintype "bidirectional"))
    )
    (net (code "121") (name "unconnected-(U1-P$56-Pad56)") (class "Default")
      (node (ref "U1") (pin "56") (pinfunction "P$56_56") (pintype "bidirectional"))
    )
    (net (code "122") (name "unconnected-(U1-P$57-Pad57)") (class "Default")
      (node (ref "U1") (pin "57") (pinfunction "P$57_57") (pintype "bidirectional"))
    )
    (net (code "123") (name "unconnected-(U1-P$58-Pad58)") (class "Default")
      (node (ref "U1") (pin "58") (pinfunction "P$58_58") (pintype "bidirectional"))
    )
    (net (code "124") (name "unconnected-(U1-P$60-Pad60)") (class "Default")
      (node (ref "U1") (pin "60") (pinfunction "P$60_60") (pintype "bidirectional"))
    )
    (net (code "125") (name "unconnected-(U1-P$61-Pad61)") (class "Default")
      (node (ref "U1") (pin "61") (pinfunction "P$61_61") (pintype "bidirectional"))
    )
    (net (code "126") (name "unconnected-(U1-P$62-Pad62)") (class "Default")
      (node (ref "U1") (pin "62") (pinfunction "P$62_62") (pintype "bidirectional"))
    )
    (net (code "127") (name "unconnected-(U1-P$67-Pad67)") (class "Default")
      (node (ref "U1") (pin "67") (pinfunction "P$67_67") (pintype "bidirectional"))
    )
    (net (code "128") (name "unconnected-(U1-P$70-Pad70)") (class "Default")
      (node (ref "U1") (pin "70") (pinfunction "P$70_70") (pintype "bidirectional"))
    )
    (net (code "129") (name "unconnected-(U1-P$71-Pad71)") (class "Default")
      (node (ref "U1") (pin "71") (pinfunction "P$71_71") (pintype "bidirectional"))
    )
    (net (code "130") (name "unconnected-(U1-P$77-Pad77)") (class "Default")
      (node (ref "U1") (pin "77") (pinfunction "P$77_77") (pintype "bidirectional"))
    )
    (net (code "131") (name "unconnected-(U1-P$84-Pad84)") (class "Default")
      (node (ref "U1") (pin "84") (pinfunction "P$84_84") (pintype "bidirectional"))
    )
    (net (code "132") (name "unconnected-(U1-P$85-Pad85)") (class "Default")
      (node (ref "U1") (pin "85") (pinfunction "P$85_85") (pintype "bidirectional"))
    )
    (net (code "133") (name "unconnected-(U1-P$88-Pad88)") (class "Default")
      (node (ref "U1") (pin "88") (pinfunction "P$88_88") (pintype "bidirectional"))
    )
    (net (code "134") (name "unconnected-(U1-P$89-Pad89)") (class "Default")
      (node (ref "U1") (pin "89") (pinfunction "P$89_89") (pintype "bidirectional"))
    )
    (net (code "135") (name "unconnected-(U1-P$90-Pad90)") (class "Default")
      (node (ref "U1") (pin "90") (pinfunction "P$90_90") (pintype "bidirectional"))
    )
    (net (code "136") (name "unconnected-(U1-P$91-Pad91)") (class "Default")
      (node (ref "U1") (pin "91") (pinfunction "P$91_91") (pintype "bidirectional"))
    )
    (net (code "137") (name "unconnected-(U1-P$95-Pad95)") (class "Default")
      (node (ref "U1") (pin "95") (pinfunction "P$95_95") (pintype "bidirectional"))
    )
    (net (code "138") (name "unconnected-(U1-P$96-Pad96)") (class "Default")
      (node (ref "U1") (pin "96") (pinfunction "P$96_96") (pintype "bidirectional"))
    )
    (net (code "139") (name "unconnected-(U1-P$98-Pad98)") (class "Default")
      (node (ref "U1") (pin "98") (pinfunction "P$98_98") (pintype "bidirectional"))
    )
    (net (code "140") (name "unconnected-(U5-GPIO0-Pad9)") (class "Default")
      (node (ref "U5") (pin "9") (pinfunction "GPIO0_9") (pintype "bidirectional"))
    )
    (net (code "141") (name "unconnected-(U5-GPIO1-Pad10)") (class "Default")
      (node (ref "U5") (pin "10") (pinfunction "GPIO1_10") (pintype "bidirectional"))
    )
    (net (code "142") (name "unconnected-(U5-GPIO2-Pad19)") (class "Default")
      (node (ref "U5") (pin "19") (pinfunction "GPIO2_19") (pintype "bidirectional"))
    )
    (net (code "143") (name "unconnected-(U5-GPIO3-Pad20)") (class "Default")
      (node (ref "U5") (pin "20") (pinfunction "GPIO3_20") (pintype "bidirectional"))
    )
    (net (code "144") (name "unconnected-(U5-TXRAMP-Pad7)") (class "Default")
      (node (ref "U5") (pin "7") (pinfunction "TXRAMP_7") (pintype "output"))
    )
    (net (code "145") (name "unconnected-(U5-XOUT-Pad16)") (class "Default")
      (node (ref "U5") (pin "16") (pinfunction "XOUT_16") (pintype "output"))
    )
    (net (code "146") (name "unconnected-(U6-PadBASE)") (class "Default")
      (node (ref "U6") (pin "BASE") (pinfunction "BASE_BASE") (pintype "bidirectional"))
    )
    (net (code "147") (name "unconnected-(X3-NC-Pad1)") (class "Default")
      (node (ref "X3") (pin "1") (pinfunction "NC_1") (pintype "input"))
    )
  )
)
